# divisor.net
KiCad netlist of a schematic drawn in Altium Designer
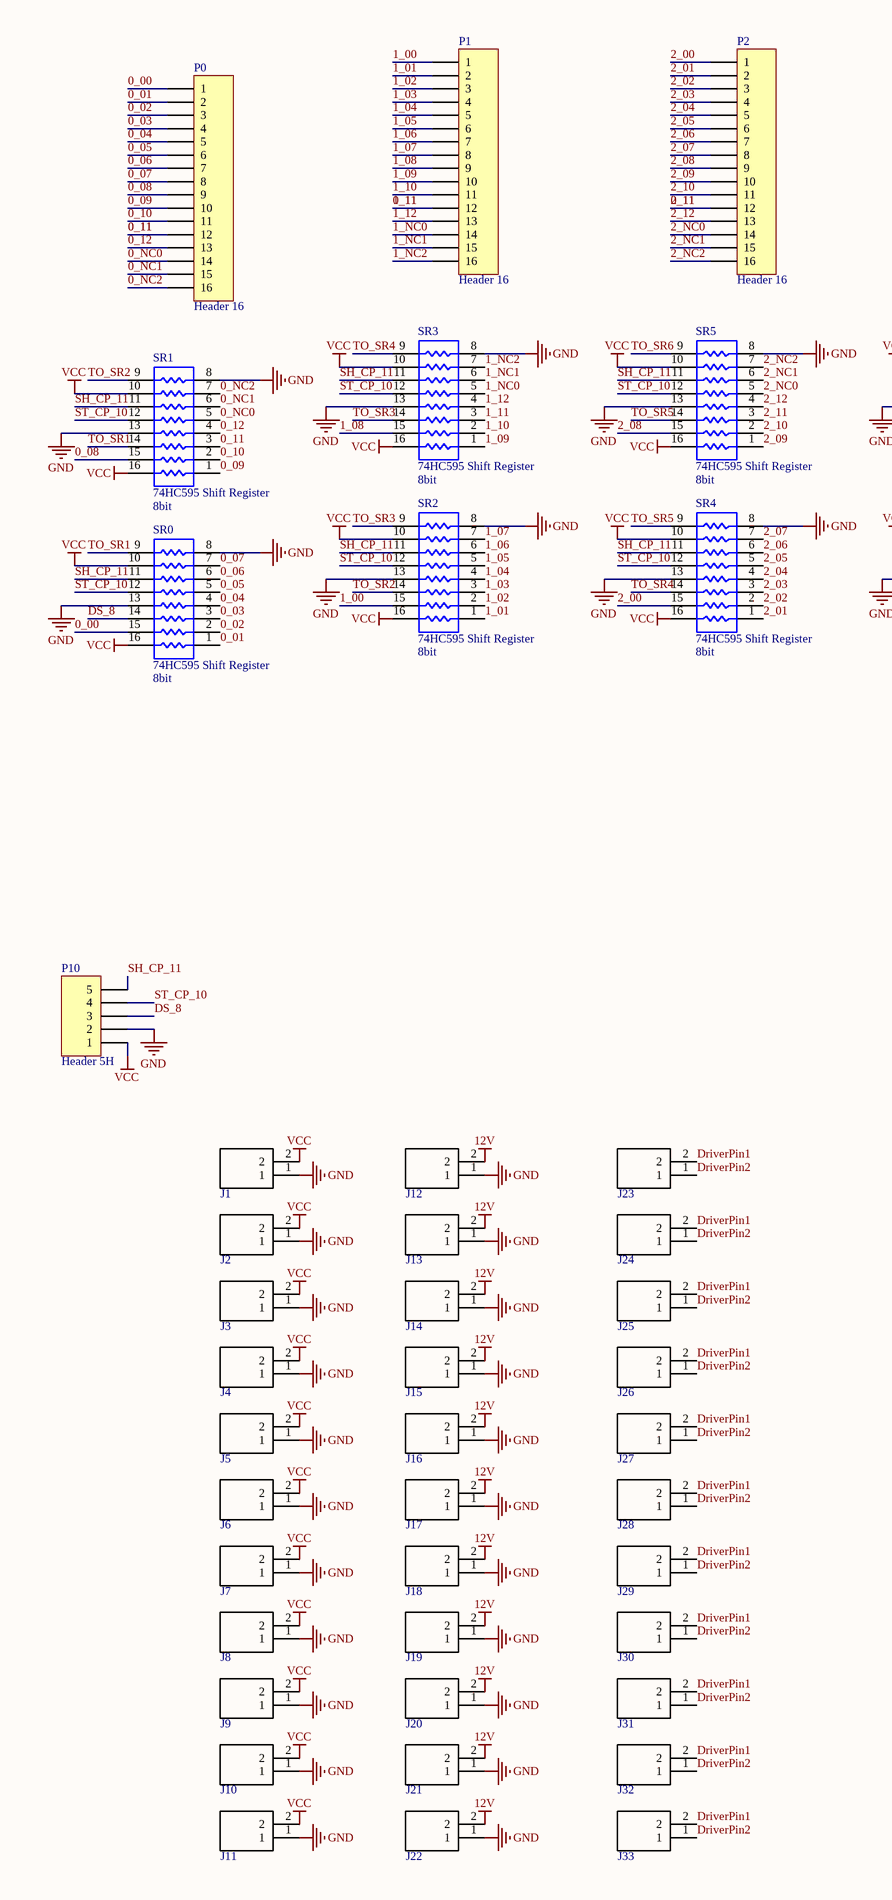
[diagram p0: divisor.SchDoc, left]
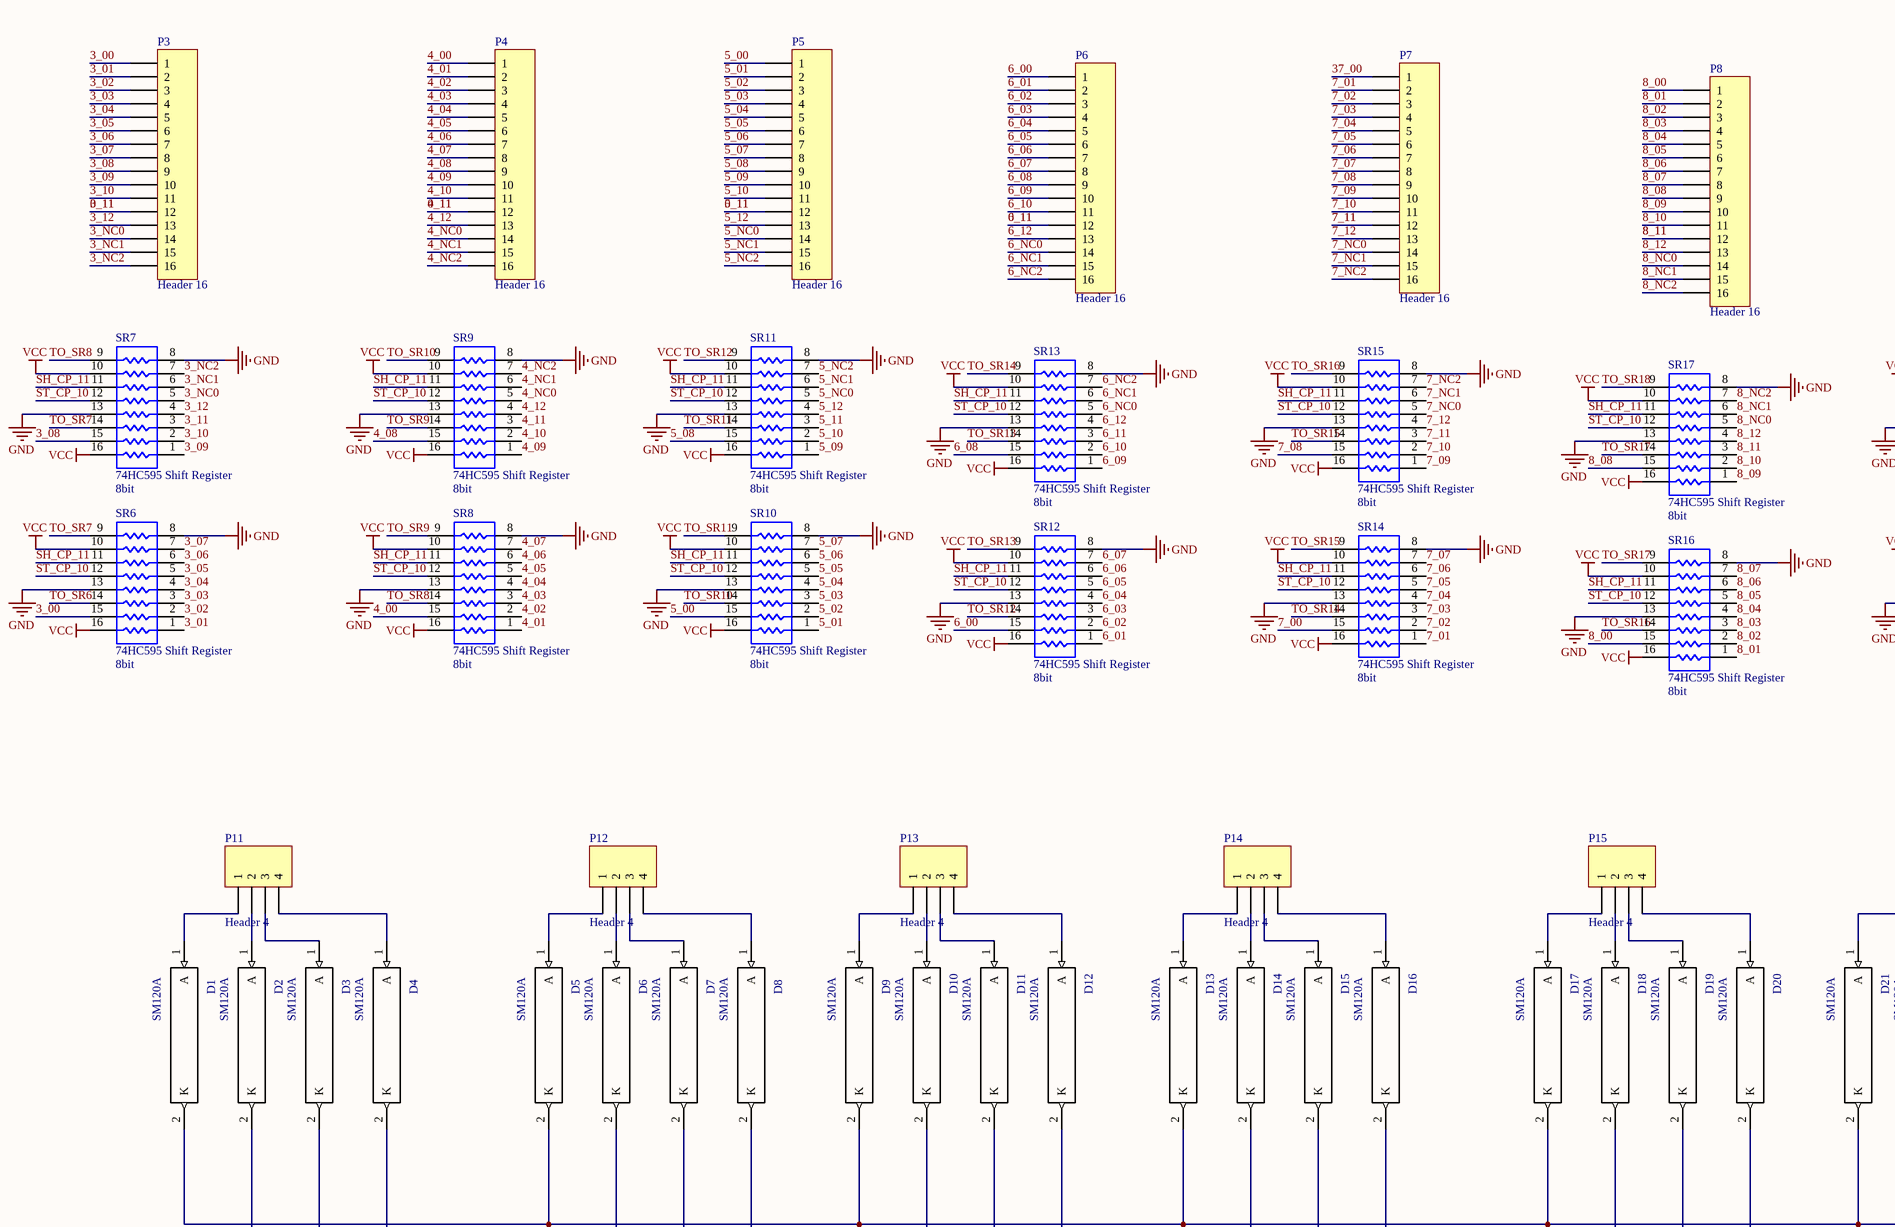
[diagram p1: divisor.SchDoc, middle]
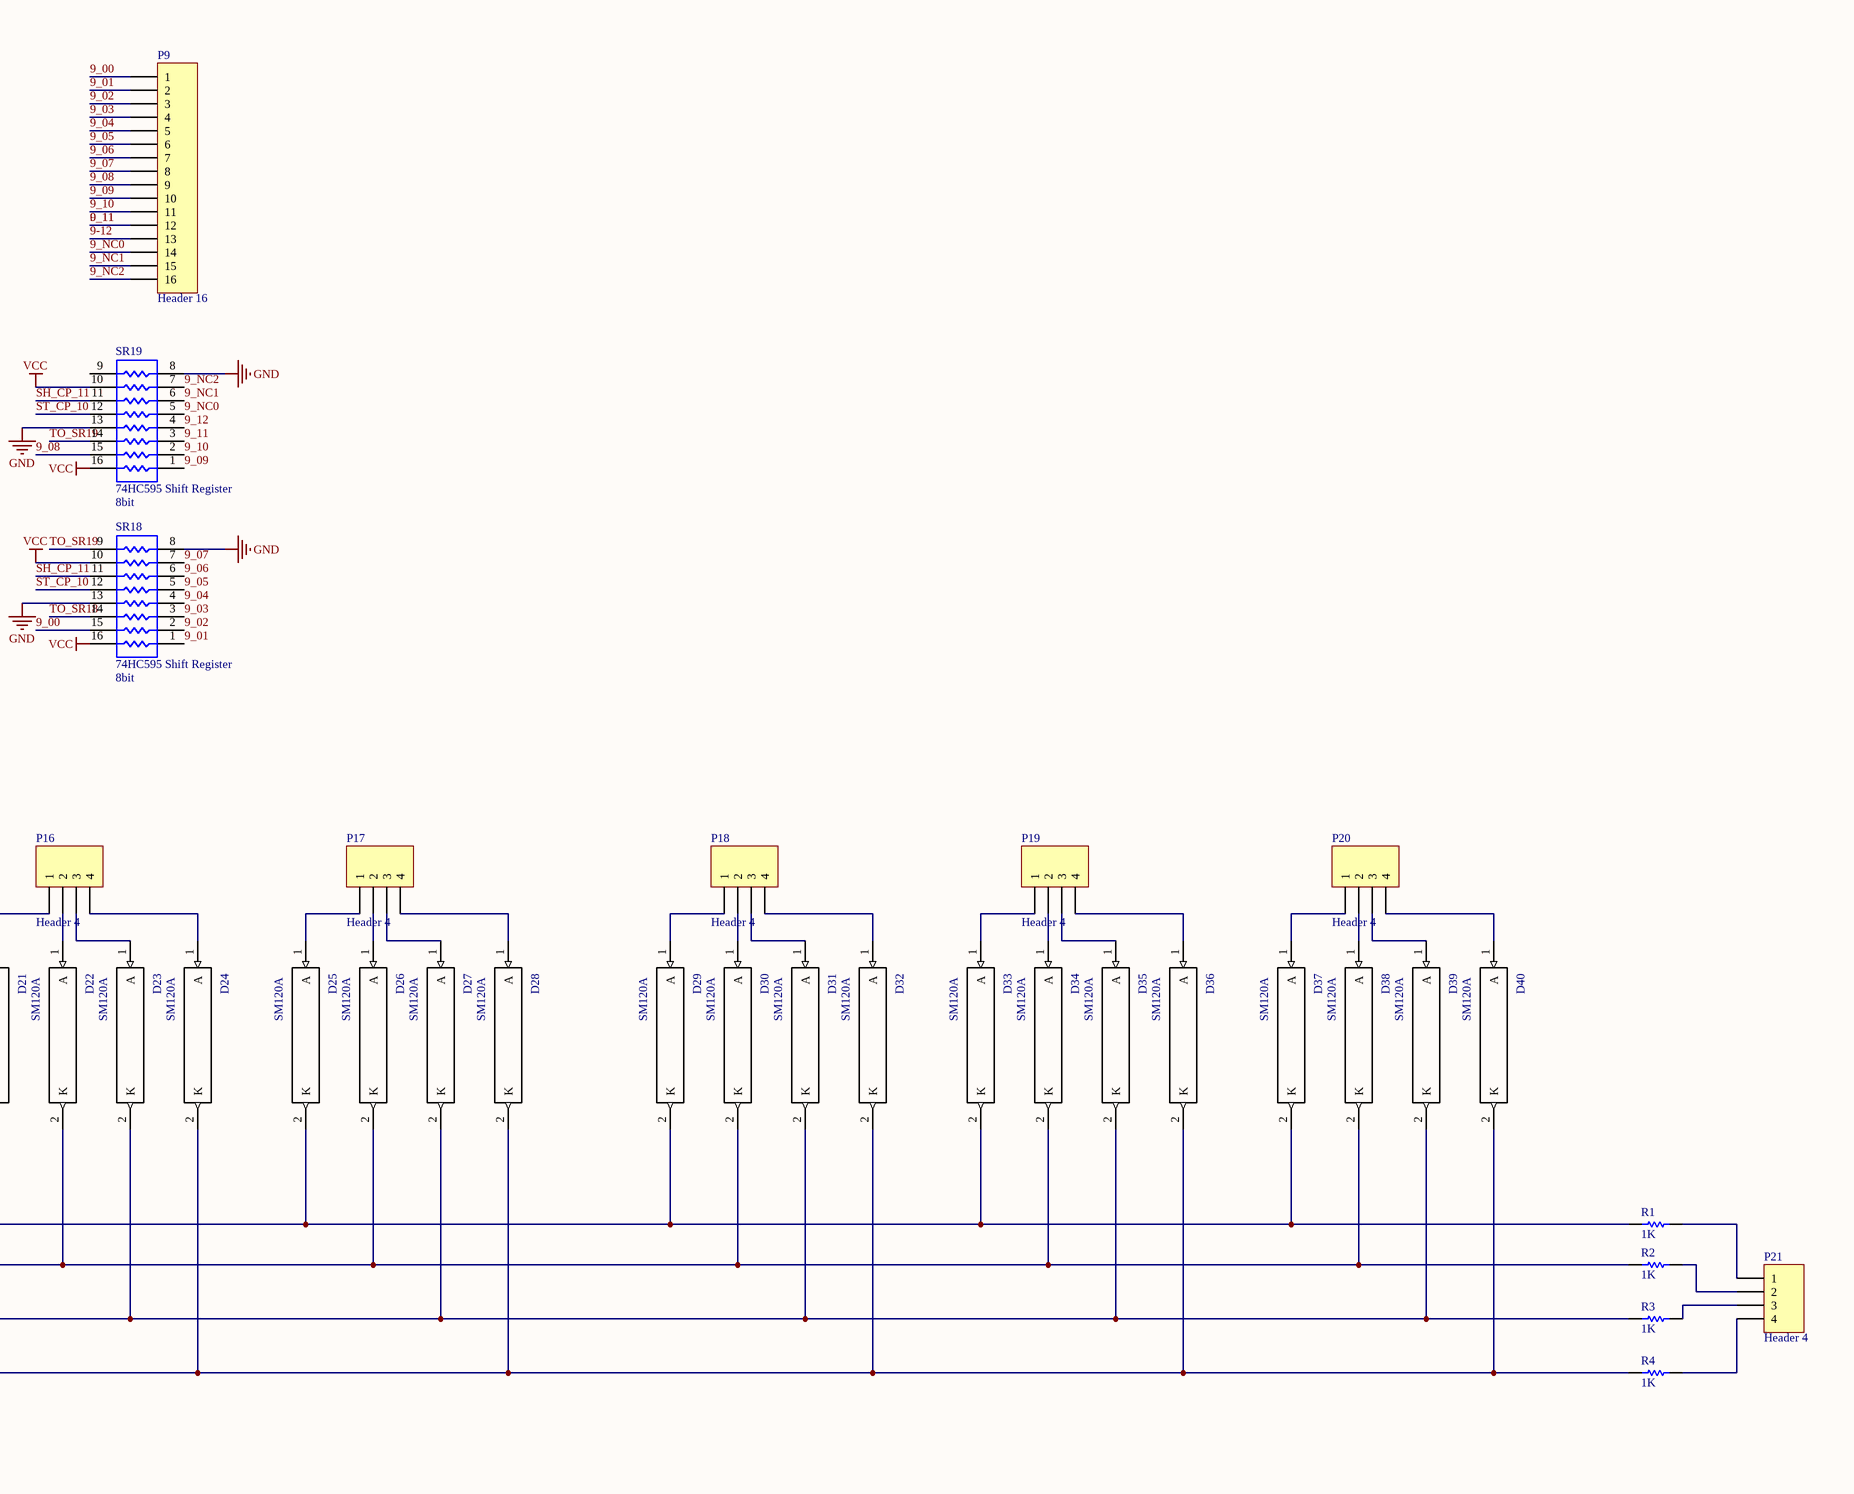
[diagram p2: divisor.SchDoc, right]

(export (version "E")
  (design (tool "Eeschema 10.0.6"))
  (components
    (comp (ref "D1")
      (value "SM120A")
      (footprint "*DIOM5227X270N_S1M(Primary)")
      (description "SCHOTTKY RECTIFIER 2A; Voltage Vrrm: 60V; Diode Case Style: DO-214AC; Case Style: DO-214AC")
      (fields (field (name "MF") "STMicroelectronics") (field (name "MP") "STPS2L60A"))
      (libsource (lib "STPS2L60A") (part "STPS2L60A"))
    )
    (comp (ref "D2")
      (value "SM120A")
      (footprint "*DIOM5227X270N_S1M(Primary)")
      (description "SCHOTTKY RECTIFIER 2A; Voltage Vrrm: 60V; Diode Case Style: DO-214AC; Case Style: DO-214AC")
      (fields (field (name "MF") "STMicroelectronics") (field (name "MP") "STPS2L60A"))
      (libsource (lib "STPS2L60A") (part "STPS2L60A"))
    )
    (comp (ref "D3")
      (value "SM120A")
      (footprint "*DIOM5227X270N_S1M(Primary)")
      (description "SCHOTTKY RECTIFIER 2A; Voltage Vrrm: 60V; Diode Case Style: DO-214AC; Case Style: DO-214AC")
      (fields (field (name "MF") "STMicroelectronics") (field (name "MP") "STPS2L60A"))
      (libsource (lib "STPS2L60A") (part "STPS2L60A"))
    )
    (comp (ref "D4")
      (value "SM120A")
      (footprint "*DIOM5227X270N_S1M(Primary)")
      (description "SCHOTTKY RECTIFIER 2A; Voltage Vrrm: 60V; Diode Case Style: DO-214AC; Case Style: DO-214AC")
      (fields (field (name "MF") "STMicroelectronics") (field (name "MP") "STPS2L60A"))
      (libsource (lib "STPS2L60A") (part "STPS2L60A"))
    )
    (comp (ref "D5")
      (value "SM120A")
      (footprint "*DIOM5227X270N_S1M(Primary)")
      (description "SCHOTTKY RECTIFIER 2A; Voltage Vrrm: 60V; Diode Case Style: DO-214AC; Case Style: DO-214AC")
      (fields (field (name "MF") "STMicroelectronics") (field (name "MP") "STPS2L60A"))
      (libsource (lib "STPS2L60A") (part "STPS2L60A"))
    )
    (comp (ref "D6")
      (value "SM120A")
      (footprint "*DIOM5227X270N_S1M(Primary)")
      (description "SCHOTTKY RECTIFIER 2A; Voltage Vrrm: 60V; Diode Case Style: DO-214AC; Case Style: DO-214AC")
      (fields (field (name "MF") "STMicroelectronics") (field (name "MP") "STPS2L60A"))
      (libsource (lib "STPS2L60A") (part "STPS2L60A"))
    )
    (comp (ref "D7")
      (value "SM120A")
      (footprint "*DIOM5227X270N_S1M(Primary)")
      (description "SCHOTTKY RECTIFIER 2A; Voltage Vrrm: 60V; Diode Case Style: DO-214AC; Case Style: DO-214AC")
      (fields (field (name "MF") "STMicroelectronics") (field (name "MP") "STPS2L60A"))
      (libsource (lib "STPS2L60A") (part "STPS2L60A"))
    )
    (comp (ref "D8")
      (value "SM120A")
      (footprint "*DIOM5227X270N_S1M(Primary)")
      (description "SCHOTTKY RECTIFIER 2A; Voltage Vrrm: 60V; Diode Case Style: DO-214AC; Case Style: DO-214AC")
      (fields (field (name "MF") "STMicroelectronics") (field (name "MP") "STPS2L60A"))
      (libsource (lib "STPS2L60A") (part "STPS2L60A"))
    )
    (comp (ref "D9")
      (value "SM120A")
      (footprint "*DIOM5227X270N_S1M(Primary)")
      (description "SCHOTTKY RECTIFIER 2A; Voltage Vrrm: 60V; Diode Case Style: DO-214AC; Case Style: DO-214AC")
      (fields (field (name "MF") "STMicroelectronics") (field (name "MP") "STPS2L60A"))
      (libsource (lib "STPS2L60A") (part "STPS2L60A"))
    )
    (comp (ref "D10")
      (value "SM120A")
      (footprint "*DIOM5227X270N_S1M(Primary)")
      (description "SCHOTTKY RECTIFIER 2A; Voltage Vrrm: 60V; Diode Case Style: DO-214AC; Case Style: DO-214AC")
      (fields (field (name "MF") "STMicroelectronics") (field (name "MP") "STPS2L60A"))
      (libsource (lib "STPS2L60A") (part "STPS2L60A"))
    )
    (comp (ref "D11")
      (value "SM120A")
      (footprint "*DIOM5227X270N_S1M(Primary)")
      (description "SCHOTTKY RECTIFIER 2A; Voltage Vrrm: 60V; Diode Case Style: DO-214AC; Case Style: DO-214AC")
      (fields (field (name "MF") "STMicroelectronics") (field (name "MP") "STPS2L60A"))
      (libsource (lib "STPS2L60A") (part "STPS2L60A"))
    )
    (comp (ref "D12")
      (value "SM120A")
      (footprint "*DIOM5227X270N_S1M(Primary)")
      (description "SCHOTTKY RECTIFIER 2A; Voltage Vrrm: 60V; Diode Case Style: DO-214AC; Case Style: DO-214AC")
      (fields (field (name "MF") "STMicroelectronics") (field (name "MP") "STPS2L60A"))
      (libsource (lib "STPS2L60A") (part "STPS2L60A"))
    )
    (comp (ref "D13")
      (value "SM120A")
      (footprint "*DIOM5227X270N_S1M(Primary)")
      (description "SCHOTTKY RECTIFIER 2A; Voltage Vrrm: 60V; Diode Case Style: DO-214AC; Case Style: DO-214AC")
      (fields (field (name "MF") "STMicroelectronics") (field (name "MP") "STPS2L60A"))
      (libsource (lib "STPS2L60A") (part "STPS2L60A"))
    )
    (comp (ref "D14")
      (value "SM120A")
      (footprint "*DIOM5227X270N_S1M(Primary)")
      (description "SCHOTTKY RECTIFIER 2A; Voltage Vrrm: 60V; Diode Case Style: DO-214AC; Case Style: DO-214AC")
      (fields (field (name "MF") "STMicroelectronics") (field (name "MP") "STPS2L60A"))
      (libsource (lib "STPS2L60A") (part "STPS2L60A"))
    )
    (comp (ref "D15")
      (value "SM120A")
      (footprint "*DIOM5227X270N_S1M(Primary)")
      (description "SCHOTTKY RECTIFIER 2A; Voltage Vrrm: 60V; Diode Case Style: DO-214AC; Case Style: DO-214AC")
      (fields (field (name "MF") "STMicroelectronics") (field (name "MP") "STPS2L60A"))
      (libsource (lib "STPS2L60A") (part "STPS2L60A"))
    )
    (comp (ref "D16")
      (value "SM120A")
      (footprint "*DIOM5227X270N_S1M(Primary)")
      (description "SCHOTTKY RECTIFIER 2A; Voltage Vrrm: 60V; Diode Case Style: DO-214AC; Case Style: DO-214AC")
      (fields (field (name "MF") "STMicroelectronics") (field (name "MP") "STPS2L60A"))
      (libsource (lib "STPS2L60A") (part "STPS2L60A"))
    )
    (comp (ref "D17")
      (value "SM120A")
      (footprint "*DIOM5227X270N_S1M(Primary)")
      (description "SCHOTTKY RECTIFIER 2A; Voltage Vrrm: 60V; Diode Case Style: DO-214AC; Case Style: DO-214AC")
      (fields (field (name "MF") "STMicroelectronics") (field (name "MP") "STPS2L60A"))
      (libsource (lib "STPS2L60A") (part "STPS2L60A"))
    )
    (comp (ref "D18")
      (value "SM120A")
      (footprint "*DIOM5227X270N_S1M(Primary)")
      (description "SCHOTTKY RECTIFIER 2A; Voltage Vrrm: 60V; Diode Case Style: DO-214AC; Case Style: DO-214AC")
      (fields (field (name "MF") "STMicroelectronics") (field (name "MP") "STPS2L60A"))
      (libsource (lib "STPS2L60A") (part "STPS2L60A"))
    )
    (comp (ref "D19")
      (value "SM120A")
      (footprint "*DIOM5227X270N_S1M(Primary)")
      (description "SCHOTTKY RECTIFIER 2A; Voltage Vrrm: 60V; Diode Case Style: DO-214AC; Case Style: DO-214AC")
      (fields (field (name "MF") "STMicroelectronics") (field (name "MP") "STPS2L60A"))
      (libsource (lib "STPS2L60A") (part "STPS2L60A"))
    )
    (comp (ref "D20")
      (value "SM120A")
      (footprint "*DIOM5227X270N_S1M(Primary)")
      (description "SCHOTTKY RECTIFIER 2A; Voltage Vrrm: 60V; Diode Case Style: DO-214AC; Case Style: DO-214AC")
      (fields (field (name "MF") "STMicroelectronics") (field (name "MP") "STPS2L60A"))
      (libsource (lib "STPS2L60A") (part "STPS2L60A"))
    )
    (comp (ref "D21")
      (value "SM120A")
      (footprint "*DIOM5227X270N_S1M(Primary)")
      (description "SCHOTTKY RECTIFIER 2A; Voltage Vrrm: 60V; Diode Case Style: DO-214AC; Case Style: DO-214AC")
      (fields (field (name "MF") "STMicroelectronics") (field (name "MP") "STPS2L60A"))
      (libsource (lib "STPS2L60A") (part "STPS2L60A"))
    )
    (comp (ref "D22")
      (value "SM120A")
      (footprint "*DIOM5227X270N_S1M(Primary)")
      (description "SCHOTTKY RECTIFIER 2A; Voltage Vrrm: 60V; Diode Case Style: DO-214AC; Case Style: DO-214AC")
      (fields (field (name "MF") "STMicroelectronics") (field (name "MP") "STPS2L60A"))
      (libsource (lib "STPS2L60A") (part "STPS2L60A"))
    )
    (comp (ref "D23")
      (value "SM120A")
      (footprint "*DIOM5227X270N_S1M(Primary)")
      (description "SCHOTTKY RECTIFIER 2A; Voltage Vrrm: 60V; Diode Case Style: DO-214AC; Case Style: DO-214AC")
      (fields (field (name "MF") "STMicroelectronics") (field (name "MP") "STPS2L60A"))
      (libsource (lib "STPS2L60A") (part "STPS2L60A"))
    )
    (comp (ref "D24")
      (value "SM120A")
      (footprint "*DIOM5227X270N_S1M(Primary)")
      (description "SCHOTTKY RECTIFIER 2A; Voltage Vrrm: 60V; Diode Case Style: DO-214AC; Case Style: DO-214AC")
      (fields (field (name "MF") "STMicroelectronics") (field (name "MP") "STPS2L60A"))
      (libsource (lib "STPS2L60A") (part "STPS2L60A"))
    )
    (comp (ref "D25")
      (value "SM120A")
      (footprint "*DIOM5227X270N_S1M(Primary)")
      (description "SCHOTTKY RECTIFIER 2A; Voltage Vrrm: 60V; Diode Case Style: DO-214AC; Case Style: DO-214AC")
      (fields (field (name "MF") "STMicroelectronics") (field (name "MP") "STPS2L60A"))
      (libsource (lib "STPS2L60A") (part "STPS2L60A"))
    )
    (comp (ref "D26")
      (value "SM120A")
      (footprint "*DIOM5227X270N_S1M(Primary)")
      (description "SCHOTTKY RECTIFIER 2A; Voltage Vrrm: 60V; Diode Case Style: DO-214AC; Case Style: DO-214AC")
      (fields (field (name "MF") "STMicroelectronics") (field (name "MP") "STPS2L60A"))
      (libsource (lib "STPS2L60A") (part "STPS2L60A"))
    )
    (comp (ref "D27")
      (value "SM120A")
      (footprint "*DIOM5227X270N_S1M(Primary)")
      (description "SCHOTTKY RECTIFIER 2A; Voltage Vrrm: 60V; Diode Case Style: DO-214AC; Case Style: DO-214AC")
      (fields (field (name "MF") "STMicroelectronics") (field (name "MP") "STPS2L60A"))
      (libsource (lib "STPS2L60A") (part "STPS2L60A"))
    )
    (comp (ref "D28")
      (value "SM120A")
      (footprint "*DIOM5227X270N_S1M(Primary)")
      (description "SCHOTTKY RECTIFIER 2A; Voltage Vrrm: 60V; Diode Case Style: DO-214AC; Case Style: DO-214AC")
      (fields (field (name "MF") "STMicroelectronics") (field (name "MP") "STPS2L60A"))
      (libsource (lib "STPS2L60A") (part "STPS2L60A"))
    )
    (comp (ref "D29")
      (value "SM120A")
      (footprint "*DIOM5227X270N_S1M(Primary)")
      (description "SCHOTTKY RECTIFIER 2A; Voltage Vrrm: 60V; Diode Case Style: DO-214AC; Case Style: DO-214AC")
      (fields (field (name "MF") "STMicroelectronics") (field (name "MP") "STPS2L60A"))
      (libsource (lib "STPS2L60A") (part "STPS2L60A"))
    )
    (comp (ref "D30")
      (value "SM120A")
      (footprint "*DIOM5227X270N_S1M(Primary)")
      (description "SCHOTTKY RECTIFIER 2A; Voltage Vrrm: 60V; Diode Case Style: DO-214AC; Case Style: DO-214AC")
      (fields (field (name "MF") "STMicroelectronics") (field (name "MP") "STPS2L60A"))
      (libsource (lib "STPS2L60A") (part "STPS2L60A"))
    )
    (comp (ref "D31")
      (value "SM120A")
      (footprint "*DIOM5227X270N_S1M(Primary)")
      (description "SCHOTTKY RECTIFIER 2A; Voltage Vrrm: 60V; Diode Case Style: DO-214AC; Case Style: DO-214AC")
      (fields (field (name "MF") "STMicroelectronics") (field (name "MP") "STPS2L60A"))
      (libsource (lib "STPS2L60A") (part "STPS2L60A"))
    )
    (comp (ref "D32")
      (value "SM120A")
      (footprint "*DIOM5227X270N_S1M(Primary)")
      (description "SCHOTTKY RECTIFIER 2A; Voltage Vrrm: 60V; Diode Case Style: DO-214AC; Case Style: DO-214AC")
      (fields (field (name "MF") "STMicroelectronics") (field (name "MP") "STPS2L60A"))
      (libsource (lib "STPS2L60A") (part "STPS2L60A"))
    )
    (comp (ref "D33")
      (value "SM120A")
      (footprint "*DIOM5227X270N_S1M(Primary)")
      (description "SCHOTTKY RECTIFIER 2A; Voltage Vrrm: 60V; Diode Case Style: DO-214AC; Case Style: DO-214AC")
      (fields (field (name "MF") "STMicroelectronics") (field (name "MP") "STPS2L60A"))
      (libsource (lib "STPS2L60A") (part "STPS2L60A"))
    )
    (comp (ref "D34")
      (value "SM120A")
      (footprint "*DIOM5227X270N_S1M(Primary)")
      (description "SCHOTTKY RECTIFIER 2A; Voltage Vrrm: 60V; Diode Case Style: DO-214AC; Case Style: DO-214AC")
      (fields (field (name "MF") "STMicroelectronics") (field (name "MP") "STPS2L60A"))
      (libsource (lib "STPS2L60A") (part "STPS2L60A"))
    )
    (comp (ref "D35")
      (value "SM120A")
      (footprint "*DIOM5227X270N_S1M(Primary)")
      (description "SCHOTTKY RECTIFIER 2A; Voltage Vrrm: 60V; Diode Case Style: DO-214AC; Case Style: DO-214AC")
      (fields (field (name "MF") "STMicroelectronics") (field (name "MP") "STPS2L60A"))
      (libsource (lib "STPS2L60A") (part "STPS2L60A"))
    )
    (comp (ref "D36")
      (value "SM120A")
      (footprint "*DIOM5227X270N_S1M(Primary)")
      (description "SCHOTTKY RECTIFIER 2A; Voltage Vrrm: 60V; Diode Case Style: DO-214AC; Case Style: DO-214AC")
      (fields (field (name "MF") "STMicroelectronics") (field (name "MP") "STPS2L60A"))
      (libsource (lib "STPS2L60A") (part "STPS2L60A"))
    )
    (comp (ref "D37")
      (value "SM120A")
      (footprint "*DIOM5227X270N_S1M(Primary)")
      (description "SCHOTTKY RECTIFIER 2A; Voltage Vrrm: 60V; Diode Case Style: DO-214AC; Case Style: DO-214AC")
      (fields (field (name "MF") "STMicroelectronics") (field (name "MP") "STPS2L60A"))
      (libsource (lib "STPS2L60A") (part "STPS2L60A"))
    )
    (comp (ref "D38")
      (value "SM120A")
      (footprint "*DIOM5227X270N_S1M(Primary)")
      (description "SCHOTTKY RECTIFIER 2A; Voltage Vrrm: 60V; Diode Case Style: DO-214AC; Case Style: DO-214AC")
      (fields (field (name "MF") "STMicroelectronics") (field (name "MP") "STPS2L60A"))
      (libsource (lib "STPS2L60A") (part "STPS2L60A"))
    )
    (comp (ref "D39")
      (value "SM120A")
      (footprint "*DIOM5227X270N_S1M(Primary)")
      (description "SCHOTTKY RECTIFIER 2A; Voltage Vrrm: 60V; Diode Case Style: DO-214AC; Case Style: DO-214AC")
      (fields (field (name "MF") "STMicroelectronics") (field (name "MP") "STPS2L60A"))
      (libsource (lib "STPS2L60A") (part "STPS2L60A"))
    )
    (comp (ref "D40")
      (value "SM120A")
      (footprint "*DIOM5227X270N_S1M(Primary)")
      (description "SCHOTTKY RECTIFIER 2A; Voltage Vrrm: 60V; Diode Case Style: DO-214AC; Case Style: DO-214AC")
      (fields (field (name "MF") "STMicroelectronics") (field (name "MP") "STPS2L60A"))
      (libsource (lib "STPS2L60A") (part "STPS2L60A"))
    )
    (comp (ref "J1")
      (value "6-1123723-2")
      (footprint "*TE_6-1123723-2")
      (description "3.96 EP HDR ASSY 2P_GREEN_")
      (fields (field (name "MF") "TE Connectivity"))
      (libsource (lib "6-1123723-2") (part "6-1123723-2"))
    )
    (comp (ref "J2")
      (value "6-1123723-2")
      (footprint "*TE_6-1123723-2")
      (description "3.96 EP HDR ASSY 2P_GREEN_")
      (fields (field (name "MF") "TE Connectivity"))
      (libsource (lib "6-1123723-2") (part "6-1123723-2"))
    )
    (comp (ref "J3")
      (value "6-1123723-2")
      (footprint "*TE_6-1123723-2")
      (description "3.96 EP HDR ASSY 2P_GREEN_")
      (fields (field (name "MF") "TE Connectivity"))
      (libsource (lib "6-1123723-2") (part "6-1123723-2"))
    )
    (comp (ref "J4")
      (value "6-1123723-2")
      (footprint "*TE_6-1123723-2")
      (description "3.96 EP HDR ASSY 2P_GREEN_")
      (fields (field (name "MF") "TE Connectivity"))
      (libsource (lib "6-1123723-2") (part "6-1123723-2"))
    )
    (comp (ref "J5")
      (value "6-1123723-2")
      (footprint "*TE_6-1123723-2")
      (description "3.96 EP HDR ASSY 2P_GREEN_")
      (fields (field (name "MF") "TE Connectivity"))
      (libsource (lib "6-1123723-2") (part "6-1123723-2"))
    )
    (comp (ref "J6")
      (value "6-1123723-2")
      (footprint "*TE_6-1123723-2")
      (description "3.96 EP HDR ASSY 2P_GREEN_")
      (fields (field (name "MF") "TE Connectivity"))
      (libsource (lib "6-1123723-2") (part "6-1123723-2"))
    )
    (comp (ref "J7")
      (value "6-1123723-2")
      (footprint "*TE_6-1123723-2")
      (description "3.96 EP HDR ASSY 2P_GREEN_")
      (fields (field (name "MF") "TE Connectivity"))
      (libsource (lib "6-1123723-2") (part "6-1123723-2"))
    )
    (comp (ref "J8")
      (value "6-1123723-2")
      (footprint "*TE_6-1123723-2")
      (description "3.96 EP HDR ASSY 2P_GREEN_")
      (fields (field (name "MF") "TE Connectivity"))
      (libsource (lib "6-1123723-2") (part "6-1123723-2"))
    )
    (comp (ref "J9")
      (value "6-1123723-2")
      (footprint "*TE_6-1123723-2")
      (description "3.96 EP HDR ASSY 2P_GREEN_")
      (fields (field (name "MF") "TE Connectivity"))
      (libsource (lib "6-1123723-2") (part "6-1123723-2"))
    )
    (comp (ref "J10")
      (value "6-1123723-2")
      (footprint "*TE_6-1123723-2")
      (description "3.96 EP HDR ASSY 2P_GREEN_")
      (fields (field (name "MF") "TE Connectivity"))
      (libsource (lib "6-1123723-2") (part "6-1123723-2"))
    )
    (comp (ref "J11")
      (value "6-1123723-2")
      (footprint "*TE_6-1123723-2")
      (description "3.96 EP HDR ASSY 2P_GREEN_")
      (fields (field (name "MF") "TE Connectivity"))
      (libsource (lib "6-1123723-2") (part "6-1123723-2"))
    )
    (comp (ref "J12")
      (value "6-1123723-2")
      (footprint "*TE_6-1123723-2")
      (description "3.96 EP HDR ASSY 2P_GREEN_")
      (fields (field (name "MF") "TE Connectivity"))
      (libsource (lib "6-1123723-2") (part "6-1123723-2"))
    )
    (comp (ref "J13")
      (value "6-1123723-2")
      (footprint "*TE_6-1123723-2")
      (description "3.96 EP HDR ASSY 2P_GREEN_")
      (fields (field (name "MF") "TE Connectivity"))
      (libsource (lib "6-1123723-2") (part "6-1123723-2"))
    )
    (comp (ref "J14")
      (value "6-1123723-2")
      (footprint "*TE_6-1123723-2")
      (description "3.96 EP HDR ASSY 2P_GREEN_")
      (fields (field (name "MF") "TE Connectivity"))
      (libsource (lib "6-1123723-2") (part "6-1123723-2"))
    )
    (comp (ref "J15")
      (value "6-1123723-2")
      (footprint "*TE_6-1123723-2")
      (description "3.96 EP HDR ASSY 2P_GREEN_")
      (fields (field (name "MF") "TE Connectivity"))
      (libsource (lib "6-1123723-2") (part "6-1123723-2"))
    )
    (comp (ref "J16")
      (value "6-1123723-2")
      (footprint "*TE_6-1123723-2")
      (description "3.96 EP HDR ASSY 2P_GREEN_")
      (fields (field (name "MF") "TE Connectivity"))
      (libsource (lib "6-1123723-2") (part "6-1123723-2"))
    )
    (comp (ref "J17")
      (value "6-1123723-2")
      (footprint "*TE_6-1123723-2")
      (description "3.96 EP HDR ASSY 2P_GREEN_")
      (fields (field (name "MF") "TE Connectivity"))
      (libsource (lib "6-1123723-2") (part "6-1123723-2"))
    )
    (comp (ref "J18")
      (value "6-1123723-2")
      (footprint "*TE_6-1123723-2")
      (description "3.96 EP HDR ASSY 2P_GREEN_")
      (fields (field (name "MF") "TE Connectivity"))
      (libsource (lib "6-1123723-2") (part "6-1123723-2"))
    )
    (comp (ref "J19")
      (value "6-1123723-2")
      (footprint "*TE_6-1123723-2")
      (description "3.96 EP HDR ASSY 2P_GREEN_")
      (fields (field (name "MF") "TE Connectivity"))
      (libsource (lib "6-1123723-2") (part "6-1123723-2"))
    )
    (comp (ref "J20")
      (value "6-1123723-2")
      (footprint "*TE_6-1123723-2")
      (description "3.96 EP HDR ASSY 2P_GREEN_")
      (fields (field (name "MF") "TE Connectivity"))
      (libsource (lib "6-1123723-2") (part "6-1123723-2"))
    )
    (comp (ref "J21")
      (value "6-1123723-2")
      (footprint "*TE_6-1123723-2")
      (description "3.96 EP HDR ASSY 2P_GREEN_")
      (fields (field (name "MF") "TE Connectivity"))
      (libsource (lib "6-1123723-2") (part "6-1123723-2"))
    )
    (comp (ref "J22")
      (value "6-1123723-2")
      (footprint "*TE_6-1123723-2")
      (description "3.96 EP HDR ASSY 2P_GREEN_")
      (fields (field (name "MF") "TE Connectivity"))
      (libsource (lib "6-1123723-2") (part "6-1123723-2"))
    )
    (comp (ref "J23")
      (value "6-1123723-2")
      (footprint "*TE_6-1123723-2")
      (description "3.96 EP HDR ASSY 2P_GREEN_")
      (fields (field (name "MF") "TE Connectivity"))
      (libsource (lib "6-1123723-2") (part "6-1123723-2"))
    )
    (comp (ref "J24")
      (value "6-1123723-2")
      (footprint "*TE_6-1123723-2")
      (description "3.96 EP HDR ASSY 2P_GREEN_")
      (fields (field (name "MF") "TE Connectivity"))
      (libsource (lib "6-1123723-2") (part "6-1123723-2"))
    )
    (comp (ref "J25")
      (value "6-1123723-2")
      (footprint "*TE_6-1123723-2")
      (description "3.96 EP HDR ASSY 2P_GREEN_")
      (fields (field (name "MF") "TE Connectivity"))
      (libsource (lib "6-1123723-2") (part "6-1123723-2"))
    )
    (comp (ref "J26")
      (value "6-1123723-2")
      (footprint "*TE_6-1123723-2")
      (description "3.96 EP HDR ASSY 2P_GREEN_")
      (fields (field (name "MF") "TE Connectivity"))
      (libsource (lib "6-1123723-2") (part "6-1123723-2"))
    )
    (comp (ref "J27")
      (value "6-1123723-2")
      (footprint "*TE_6-1123723-2")
      (description "3.96 EP HDR ASSY 2P_GREEN_")
      (fields (field (name "MF") "TE Connectivity"))
      (libsource (lib "6-1123723-2") (part "6-1123723-2"))
    )
    (comp (ref "J28")
      (value "6-1123723-2")
      (footprint "*TE_6-1123723-2")
      (description "3.96 EP HDR ASSY 2P_GREEN_")
      (fields (field (name "MF") "TE Connectivity"))
      (libsource (lib "6-1123723-2") (part "6-1123723-2"))
    )
    (comp (ref "J29")
      (value "6-1123723-2")
      (footprint "*TE_6-1123723-2")
      (description "3.96 EP HDR ASSY 2P_GREEN_")
      (fields (field (name "MF") "TE Connectivity"))
      (libsource (lib "6-1123723-2") (part "6-1123723-2"))
    )
    (comp (ref "J30")
      (value "6-1123723-2")
      (footprint "*TE_6-1123723-2")
      (description "3.96 EP HDR ASSY 2P_GREEN_")
      (fields (field (name "MF") "TE Connectivity"))
      (libsource (lib "6-1123723-2") (part "6-1123723-2"))
    )
    (comp (ref "J31")
      (value "6-1123723-2")
      (footprint "*TE_6-1123723-2")
      (description "3.96 EP HDR ASSY 2P_GREEN_")
      (fields (field (name "MF") "TE Connectivity"))
      (libsource (lib "6-1123723-2") (part "6-1123723-2"))
    )
    (comp (ref "J32")
      (value "6-1123723-2")
      (footprint "*TE_6-1123723-2")
      (description "3.96 EP HDR ASSY 2P_GREEN_")
      (fields (field (name "MF") "TE Connectivity"))
      (libsource (lib "6-1123723-2") (part "6-1123723-2"))
    )
    (comp (ref "J33")
      (value "6-1123723-2")
      (footprint "*TE_6-1123723-2")
      (description "3.96 EP HDR ASSY 2P_GREEN_")
      (fields (field (name "MF") "TE Connectivity"))
      (libsource (lib "6-1123723-2") (part "6-1123723-2"))
    )
    (comp (ref "P0")
      (value "Header 16")
      (footprint "HDR1X16")
      (description "Header, 16-Pin")
      (fields (field (name "PUBLISHER") "Altium Limited"))
      (libsource (lib "Miscellaneous Connectors") (part "Header 16"))
    )
    (comp (ref "P1")
      (value "Header 16")
      (footprint "HDR1X16")
      (description "Header, 16-Pin")
      (fields (field (name "PUBLISHER") "Altium Limited"))
      (libsource (lib "Miscellaneous Connectors") (part "Header 16"))
    )
    (comp (ref "P2")
      (value "Header 16")
      (footprint "HDR1X16")
      (description "Header, 16-Pin")
      (fields (field (name "PUBLISHER") "Altium Limited"))
      (libsource (lib "Miscellaneous Connectors") (part "Header 16"))
    )
    (comp (ref "P3")
      (value "Header 16")
      (footprint "HDR1X16")
      (description "Header, 16-Pin")
      (fields (field (name "PUBLISHER") "Altium Limited"))
      (libsource (lib "Miscellaneous Connectors") (part "Header 16"))
    )
    (comp (ref "P4")
      (value "Header 16")
      (footprint "HDR1X16")
      (description "Header, 16-Pin")
      (fields (field (name "PUBLISHER") "Altium Limited"))
      (libsource (lib "Miscellaneous Connectors") (part "Header 16"))
    )
    (comp (ref "P5")
      (value "Header 16")
      (footprint "HDR1X16")
      (description "Header, 16-Pin")
      (fields (field (name "PUBLISHER") "Altium Limited"))
      (libsource (lib "Miscellaneous Connectors") (part "Header 16"))
    )
    (comp (ref "P6")
      (value "Header 16")
      (footprint "HDR1X16")
      (description "Header, 16-Pin")
      (fields (field (name "PUBLISHER") "Altium Limited"))
      (libsource (lib "Miscellaneous Connectors") (part "Header 16"))
    )
    (comp (ref "P7")
      (value "Header 16")
      (footprint "HDR1X16")
      (description "Header, 16-Pin")
      (fields (field (name "PUBLISHER") "Altium Limited"))
      (libsource (lib "Miscellaneous Connectors") (part "Header 16"))
    )
    (comp (ref "P8")
      (value "Header 16")
      (footprint "HDR1X16")
      (description "Header, 16-Pin")
      (fields (field (name "PUBLISHER") "Altium Limited"))
      (libsource (lib "Miscellaneous Connectors") (part "Header 16"))
    )
    (comp (ref "P9")
      (value "Header 16")
      (footprint "HDR1X16")
      (description "Header, 16-Pin")
      (fields (field (name "PUBLISHER") "Altium Limited"))
      (libsource (lib "Miscellaneous Connectors") (part "Header 16"))
    )
    (comp (ref "P10")
      (value "Header 5H")
      (footprint "hdr1x5")
      (description "Header, 5-Pin, Right Angle")
      (fields (field (name "PUBLISHER") "Altium Limited"))
      (libsource (lib "Miscellaneous Connectors") (part "Header 5H"))
    )
    (comp (ref "P11")
      (value "Header 4")
      (footprint "HDR1X4")
      (description "Header, 4-Pin")
      (fields (field (name "PUBLISHER") "Altium Limited"))
      (libsource (lib "Miscellaneous Connectors") (part "Header 4"))
    )
    (comp (ref "P12")
      (value "Header 4")
      (footprint "HDR1X4")
      (description "Header, 4-Pin")
      (fields (field (name "PUBLISHER") "Altium Limited"))
      (libsource (lib "Miscellaneous Connectors") (part "Header 4"))
    )
    (comp (ref "P13")
      (value "Header 4")
      (footprint "HDR1X4")
      (description "Header, 4-Pin")
      (fields (field (name "PUBLISHER") "Altium Limited"))
      (libsource (lib "Miscellaneous Connectors") (part "Header 4"))
    )
    (comp (ref "P14")
      (value "Header 4")
      (footprint "HDR1X4")
      (description "Header, 4-Pin")
      (fields (field (name "PUBLISHER") "Altium Limited"))
      (libsource (lib "Miscellaneous Connectors") (part "Header 4"))
    )
    (comp (ref "P15")
      (value "Header 4")
      (footprint "HDR1X4")
      (description "Header, 4-Pin")
      (fields (field (name "PUBLISHER") "Altium Limited"))
      (libsource (lib "Miscellaneous Connectors") (part "Header 4"))
    )
    (comp (ref "P16")
      (value "Header 4")
      (footprint "HDR1X4")
      (description "Header, 4-Pin")
      (fields (field (name "PUBLISHER") "Altium Limited"))
      (libsource (lib "Miscellaneous Connectors") (part "Header 4"))
    )
    (comp (ref "P17")
      (value "Header 4")
      (footprint "HDR1X4")
      (description "Header, 4-Pin")
      (fields (field (name "PUBLISHER") "Altium Limited"))
      (libsource (lib "Miscellaneous Connectors") (part "Header 4"))
    )
    (comp (ref "P18")
      (value "Header 4")
      (footprint "HDR1X4")
      (description "Header, 4-Pin")
      (fields (field (name "PUBLISHER") "Altium Limited"))
      (libsource (lib "Miscellaneous Connectors") (part "Header 4"))
    )
    (comp (ref "P19")
      (value "Header 4")
      (footprint "HDR1X4")
      (description "Header, 4-Pin")
      (fields (field (name "PUBLISHER") "Altium Limited"))
      (libsource (lib "Miscellaneous Connectors") (part "Header 4"))
    )
    (comp (ref "P20")
      (value "Header 4")
      (footprint "HDR1X4")
      (description "Header, 4-Pin")
      (fields (field (name "PUBLISHER") "Altium Limited"))
      (libsource (lib "Miscellaneous Connectors") (part "Header 4"))
    )
    (comp (ref "P21")
      (value "Header 4")
      (footprint "HDR1X4")
      (description "Header, 4-Pin")
      (fields (field (name "PUBLISHER") "Altium Limited"))
      (libsource (lib "") (part "Header 4_1"))
    )
    (comp (ref "R1")
      (value "1K")
      (footprint "6-0805_L")
      (description "Resistor")
      (fields (field (name "Comment") "Res1") (field (name "PUBLISHER") "Altium Limited"))
      (libsource (lib "Miscellaneous Devices") (part "Res1"))
    )
    (comp (ref "R2")
      (value "1K")
      (footprint "6-0805_L")
      (description "Resistor")
      (fields (field (name "Comment") "Res1") (field (name "PUBLISHER") "Altium Limited"))
      (libsource (lib "Miscellaneous Devices") (part "Res1"))
    )
    (comp (ref "R3")
      (value "1K")
      (footprint "6-0805_L")
      (description "Resistor")
      (fields (field (name "Comment") "Res1") (field (name "PUBLISHER") "Altium Limited"))
      (libsource (lib "Miscellaneous Devices") (part "Res1"))
    )
    (comp (ref "R4")
      (value "1K")
      (footprint "6-0805_L")
      (description "Resistor")
      (fields (field (name "Comment") "Res1") (field (name "PUBLISHER") "Altium Limited"))
      (libsource (lib "Miscellaneous Devices") (part "Res1"))
    )
    (comp (ref "SR0")
      (value "74HC595 Shift Register")
      (footprint "SO-16_L")
      (description "Isolated Resistor Network")
      (fields (field (name "ALTIUM_VALUE") "8bit") (field (name "PUBLISHER") "Altium Limited"))
      (libsource (lib "Miscellaneous Devices") (part "Res Pack3"))
    )
    (comp (ref "SR1")
      (value "74HC595 Shift Register")
      (footprint "SO-16_L")
      (description "Isolated Resistor Network")
      (fields (field (name "ALTIUM_VALUE") "8bit") (field (name "PUBLISHER") "Altium Limited"))
      (libsource (lib "Miscellaneous Devices") (part "Res Pack3"))
    )
    (comp (ref "SR2")
      (value "74HC595 Shift Register")
      (footprint "SO-16_L")
      (description "Isolated Resistor Network")
      (fields (field (name "ALTIUM_VALUE") "8bit") (field (name "PUBLISHER") "Altium Limited"))
      (libsource (lib "Miscellaneous Devices") (part "Res Pack3"))
    )
    (comp (ref "SR3")
      (value "74HC595 Shift Register")
      (footprint "SO-16_L")
      (description "Isolated Resistor Network")
      (fields (field (name "ALTIUM_VALUE") "8bit") (field (name "PUBLISHER") "Altium Limited"))
      (libsource (lib "Miscellaneous Devices") (part "Res Pack3"))
    )
    (comp (ref "SR4")
      (value "74HC595 Shift Register")
      (footprint "SO-16_L")
      (description "Isolated Resistor Network")
      (fields (field (name "ALTIUM_VALUE") "8bit") (field (name "PUBLISHER") "Altium Limited"))
      (libsource (lib "Miscellaneous Devices") (part "Res Pack3"))
    )
    (comp (ref "SR5")
      (value "74HC595 Shift Register")
      (footprint "SO-16_L")
      (description "Isolated Resistor Network")
      (fields (field (name "ALTIUM_VALUE") "8bit") (field (name "PUBLISHER") "Altium Limited"))
      (libsource (lib "Miscellaneous Devices") (part "Res Pack3"))
    )
    (comp (ref "SR6")
      (value "74HC595 Shift Register")
      (footprint "SO-16_L")
      (description "Isolated Resistor Network")
      (fields (field (name "ALTIUM_VALUE") "8bit") (field (name "PUBLISHER") "Altium Limited"))
      (libsource (lib "Miscellaneous Devices") (part "Res Pack3"))
    )
    (comp (ref "SR7")
      (value "74HC595 Shift Register")
      (footprint "SO-16_L")
      (description "Isolated Resistor Network")
      (fields (field (name "ALTIUM_VALUE") "8bit") (field (name "PUBLISHER") "Altium Limited"))
      (libsource (lib "Miscellaneous Devices") (part "Res Pack3"))
    )
    (comp (ref "SR8")
      (value "74HC595 Shift Register")
      (footprint "SO-16_L")
      (description "Isolated Resistor Network")
      (fields (field (name "ALTIUM_VALUE") "8bit") (field (name "PUBLISHER") "Altium Limited"))
      (libsource (lib "Miscellaneous Devices") (part "Res Pack3"))
    )
    (comp (ref "SR9")
      (value "74HC595 Shift Register")
      (footprint "SO-16_L")
      (description "Isolated Resistor Network")
      (fields (field (name "ALTIUM_VALUE") "8bit") (field (name "PUBLISHER") "Altium Limited"))
      (libsource (lib "Miscellaneous Devices") (part "Res Pack3"))
    )
    (comp (ref "SR10")
      (value "74HC595 Shift Register")
      (footprint "SO-16_L")
      (description "Isolated Resistor Network")
      (fields (field (name "ALTIUM_VALUE") "8bit") (field (name "PUBLISHER") "Altium Limited"))
      (libsource (lib "Miscellaneous Devices") (part "Res Pack3"))
    )
    (comp (ref "SR11")
      (value "74HC595 Shift Register")
      (footprint "SO-16_L")
      (description "Isolated Resistor Network")
      (fields (field (name "ALTIUM_VALUE") "8bit") (field (name "PUBLISHER") "Altium Limited"))
      (libsource (lib "Miscellaneous Devices") (part "Res Pack3"))
    )
    (comp (ref "SR12")
      (value "74HC595 Shift Register")
      (footprint "SO-16_L")
      (description "Isolated Resistor Network")
      (fields (field (name "ALTIUM_VALUE") "8bit") (field (name "PUBLISHER") "Altium Limited"))
      (libsource (lib "Miscellaneous Devices") (part "Res Pack3"))
    )
    (comp (ref "SR13")
      (value "74HC595 Shift Register")
      (footprint "SO-16_L")
      (description "Isolated Resistor Network")
      (fields (field (name "ALTIUM_VALUE") "8bit") (field (name "PUBLISHER") "Altium Limited"))
      (libsource (lib "Miscellaneous Devices") (part "Res Pack3"))
    )
    (comp (ref "SR14")
      (value "74HC595 Shift Register")
      (footprint "SO-16_L")
      (description "Isolated Resistor Network")
      (fields (field (name "ALTIUM_VALUE") "8bit") (field (name "PUBLISHER") "Altium Limited"))
      (libsource (lib "Miscellaneous Devices") (part "Res Pack3"))
    )
    (comp (ref "SR15")
      (value "74HC595 Shift Register")
      (footprint "SO-16_L")
      (description "Isolated Resistor Network")
      (fields (field (name "ALTIUM_VALUE") "8bit") (field (name "PUBLISHER") "Altium Limited"))
      (libsource (lib "Miscellaneous Devices") (part "Res Pack3"))
    )
    (comp (ref "SR16")
      (value "74HC595 Shift Register")
      (footprint "SO-16_L")
      (description "Isolated Resistor Network")
      (fields (field (name "ALTIUM_VALUE") "8bit") (field (name "PUBLISHER") "Altium Limited"))
      (libsource (lib "Miscellaneous Devices") (part "Res Pack3"))
    )
    (comp (ref "SR17")
      (value "74HC595 Shift Register")
      (footprint "SO-16_L")
      (description "Isolated Resistor Network")
      (fields (field (name "ALTIUM_VALUE") "8bit") (field (name "PUBLISHER") "Altium Limited"))
      (libsource (lib "Miscellaneous Devices") (part "Res Pack3"))
    )
    (comp (ref "SR18")
      (value "74HC595 Shift Register")
      (footprint "SO-16_L")
      (description "Isolated Resistor Network")
      (fields (field (name "ALTIUM_VALUE") "8bit") (field (name "PUBLISHER") "Altium Limited"))
      (libsource (lib "Miscellaneous Devices") (part "Res Pack3"))
    )
    (comp (ref "SR19")
      (value "74HC595 Shift Register")
      (footprint "SO-16_L")
      (description "Isolated Resistor Network")
      (fields (field (name "ALTIUM_VALUE") "8bit") (field (name "PUBLISHER") "Altium Limited"))
      (libsource (lib "Miscellaneous Devices") (part "Res Pack3"))
    )
  )
  (nets
    (net (code "1") (name "/0_00") (class "Default")
      (node (ref "P0") (pin "1") (pinfunction "1_1") (pintype "passive"))
      (node (ref "SR0") (pin "15") (pinfunction "15_15") (pintype "passive"))
    )
    (net (code "2") (name "/0_01") (class "Default")
      (node (ref "P0") (pin "2") (pinfunction "2_2") (pintype "passive"))
      (node (ref "SR0") (pin "1") (pinfunction "1_1") (pintype "passive"))
    )
    (net (code "3") (name "/0_02") (class "Default")
      (node (ref "P0") (pin "3") (pinfunction "3_3") (pintype "passive"))
      (node (ref "SR0") (pin "2") (pinfunction "2_2") (pintype "passive"))
    )
    (net (code "4") (name "/0_03") (class "Default")
      (node (ref "P0") (pin "4") (pinfunction "4_4") (pintype "passive"))
      (node (ref "SR0") (pin "3") (pinfunction "3_3") (pintype "passive"))
    )
    (net (code "5") (name "/0_04") (class "Default")
      (node (ref "P0") (pin "5") (pinfunction "5_5") (pintype "passive"))
      (node (ref "SR0") (pin "4") (pinfunction "4_4") (pintype "passive"))
    )
    (net (code "6") (name "/0_05") (class "Default")
      (node (ref "P0") (pin "6") (pinfunction "6_6") (pintype "passive"))
      (node (ref "SR0") (pin "5") (pinfunction "5_5") (pintype "passive"))
    )
    (net (code "7") (name "/0_06") (class "Default")
      (node (ref "P0") (pin "7") (pinfunction "7_7") (pintype "passive"))
      (node (ref "SR0") (pin "6") (pinfunction "6_6") (pintype "passive"))
    )
    (net (code "8") (name "/0_07") (class "Default")
      (node (ref "P0") (pin "8") (pinfunction "8_8") (pintype "passive"))
      (node (ref "SR0") (pin "7") (pinfunction "7_7") (pintype "passive"))
    )
    (net (code "9") (name "/0_08") (class "Default")
      (node (ref "P0") (pin "9") (pinfunction "9_9") (pintype "passive"))
      (node (ref "SR1") (pin "15") (pinfunction "15_15") (pintype "passive"))
    )
    (net (code "10") (name "/0_09") (class "Default")
      (node (ref "P0") (pin "10") (pinfunction "10_10") (pintype "passive"))
      (node (ref "SR1") (pin "1") (pinfunction "1_1") (pintype "passive"))
    )
    (net (code "11") (name "/0_10") (class "Default")
      (node (ref "P0") (pin "11") (pinfunction "11_11") (pintype "passive"))
      (node (ref "SR1") (pin "2") (pinfunction "2_2") (pintype "passive"))
    )
    (net (code "12") (name "/0_11") (class "Default")
      (node (ref "P0") (pin "12") (pinfunction "12_12") (pintype "passive"))
      (node (ref "P1") (pin "12") (pinfunction "12_12") (pintype "passive"))
      (node (ref "P2") (pin "12") (pinfunction "12_12") (pintype "passive"))
      (node (ref "P3") (pin "12") (pinfunction "12_12") (pintype "passive"))
      (node (ref "P4") (pin "12") (pinfunction "12_12") (pintype "passive"))
      (node (ref "P5") (pin "12") (pinfunction "12_12") (pintype "passive"))
      (node (ref "P6") (pin "12") (pinfunction "12_12") (pintype "passive"))
      (node (ref "P9") (pin "12") (pinfunction "12_12") (pintype "passive"))
      (node (ref "SR1") (pin "3") (pinfunction "3_3") (pintype "passive"))
      (node (ref "SR11") (pin "3") (pinfunction "3_3") (pintype "passive"))
      (node (ref "SR13") (pin "3") (pinfunction "3_3") (pintype "passive"))
      (node (ref "SR19") (pin "3") (pinfunction "3_3") (pintype "passive"))
      (node (ref "SR3") (pin "3") (pinfunction "3_3") (pintype "passive"))
      (node (ref "SR5") (pin "3") (pinfunction "3_3") (pintype "passive"))
      (node (ref "SR7") (pin "3") (pinfunction "3_3") (pintype "passive"))
      (node (ref "SR9") (pin "3") (pinfunction "3_3") (pintype "passive"))
    )
    (net (code "13") (name "/0_12") (class "Default")
      (node (ref "P0") (pin "13") (pinfunction "13_13") (pintype "passive"))
      (node (ref "SR1") (pin "4") (pinfunction "4_4") (pintype "passive"))
    )
    (net (code "14") (name "/0_NC0") (class "Default")
      (node (ref "P0") (pin "14") (pinfunction "14_14") (pintype "passive"))
      (node (ref "SR1") (pin "5") (pinfunction "5_5") (pintype "passive"))
    )
    (net (code "15") (name "/0_NC1") (class "Default")
      (node (ref "P0") (pin "15") (pinfunction "15_15") (pintype "passive"))
      (node (ref "SR1") (pin "6") (pinfunction "6_6") (pintype "passive"))
    )
    (net (code "16") (name "/0_NC2") (class "Default")
      (node (ref "P0") (pin "16") (pinfunction "16_16") (pintype "passive"))
      (node (ref "SR1") (pin "7") (pinfunction "7_7") (pintype "passive"))
    )
    (net (code "17") (name "/1_00") (class "Default")
      (node (ref "P1") (pin "1") (pinfunction "1_1") (pintype "passive"))
      (node (ref "SR2") (pin "15") (pinfunction "15_15") (pintype "passive"))
    )
    (net (code "18") (name "/1_01") (class "Default")
      (node (ref "P1") (pin "2") (pinfunction "2_2") (pintype "passive"))
      (node (ref "SR2") (pin "1") (pinfunction "1_1") (pintype "passive"))
    )
    (net (code "19") (name "/1_02") (class "Default")
      (node (ref "P1") (pin "3") (pinfunction "3_3") (pintype "passive"))
      (node (ref "SR2") (pin "2") (pinfunction "2_2") (pintype "passive"))
    )
    (net (code "20") (name "/1_03") (class "Default")
      (node (ref "P1") (pin "4") (pinfunction "4_4") (pintype "passive"))
      (node (ref "SR2") (pin "3") (pinfunction "3_3") (pintype "passive"))
    )
    (net (code "21") (name "/1_04") (class "Default")
      (node (ref "P1") (pin "5") (pinfunction "5_5") (pintype "passive"))
      (node (ref "SR2") (pin "4") (pinfunction "4_4") (pintype "passive"))
    )
    (net (code "22") (name "/1_05") (class "Default")
      (node (ref "P1") (pin "6") (pinfunction "6_6") (pintype "passive"))
      (node (ref "SR2") (pin "5") (pinfunction "5_5") (pintype "passive"))
    )
    (net (code "23") (name "/1_06") (class "Default")
      (node (ref "P1") (pin "7") (pinfunction "7_7") (pintype "passive"))
      (node (ref "SR2") (pin "6") (pinfunction "6_6") (pintype "passive"))
    )
    (net (code "24") (name "/1_07") (class "Default")
      (node (ref "P1") (pin "8") (pinfunction "8_8") (pintype "passive"))
      (node (ref "SR2") (pin "7") (pinfunction "7_7") (pintype "passive"))
    )
    (net (code "25") (name "/1_08") (class "Default")
      (node (ref "P1") (pin "9") (pinfunction "9_9") (pintype "passive"))
      (node (ref "SR3") (pin "15") (pinfunction "15_15") (pintype "passive"))
    )
    (net (code "26") (name "/1_09") (class "Default")
      (node (ref "P1") (pin "10") (pinfunction "10_10") (pintype "passive"))
      (node (ref "SR3") (pin "1") (pinfunction "1_1") (pintype "passive"))
    )
    (net (code "27") (name "/1_10") (class "Default")
      (node (ref "P1") (pin "11") (pinfunction "11_11") (pintype "passive"))
      (node (ref "SR3") (pin "2") (pinfunction "2_2") (pintype "passive"))
    )
    (net (code "28") (name "/1_12") (class "Default")
      (node (ref "P1") (pin "13") (pinfunction "13_13") (pintype "passive"))
      (node (ref "SR3") (pin "4") (pinfunction "4_4") (pintype "passive"))
    )
    (net (code "29") (name "/1_NC0") (class "Default")
      (node (ref "P1") (pin "14") (pinfunction "14_14") (pintype "passive"))
      (node (ref "SR3") (pin "5") (pinfunction "5_5") (pintype "passive"))
    )
    (net (code "30") (name "/1_NC1") (class "Default")
      (node (ref "P1") (pin "15") (pinfunction "15_15") (pintype "passive"))
      (node (ref "SR3") (pin "6") (pinfunction "6_6") (pintype "passive"))
    )
    (net (code "31") (name "/1_NC2") (class "Default")
      (node (ref "P1") (pin "16") (pinfunction "16_16") (pintype "passive"))
      (node (ref "SR3") (pin "7") (pinfunction "7_7") (pintype "passive"))
    )
    (net (code "32") (name "/2_00") (class "Default")
      (node (ref "P2") (pin "1") (pinfunction "1_1") (pintype "passive"))
      (node (ref "SR4") (pin "15") (pinfunction "15_15") (pintype "passive"))
    )
    (net (code "33") (name "/2_01") (class "Default")
      (node (ref "P2") (pin "2") (pinfunction "2_2") (pintype "passive"))
      (node (ref "SR4") (pin "1") (pinfunction "1_1") (pintype "passive"))
    )
    (net (code "34") (name "/2_02") (class "Default")
      (node (ref "P2") (pin "3") (pinfunction "3_3") (pintype "passive"))
      (node (ref "SR4") (pin "2") (pinfunction "2_2") (pintype "passive"))
    )
    (net (code "35") (name "/2_03") (class "Default")
      (node (ref "P2") (pin "4") (pinfunction "4_4") (pintype "passive"))
      (node (ref "SR4") (pin "3") (pinfunction "3_3") (pintype "passive"))
    )
    (net (code "36") (name "/2_04") (class "Default")
      (node (ref "P2") (pin "5") (pinfunction "5_5") (pintype "passive"))
      (node (ref "SR4") (pin "4") (pinfunction "4_4") (pintype "passive"))
    )
    (net (code "37") (name "/2_05") (class "Default")
      (node (ref "P2") (pin "6") (pinfunction "6_6") (pintype "passive"))
      (node (ref "SR4") (pin "5") (pinfunction "5_5") (pintype "passive"))
    )
    (net (code "38") (name "/2_06") (class "Default")
      (node (ref "P2") (pin "7") (pinfunction "7_7") (pintype "passive"))
      (node (ref "SR4") (pin "6") (pinfunction "6_6") (pintype "passive"))
    )
    (net (code "39") (name "/2_07") (class "Default")
      (node (ref "P2") (pin "8") (pinfunction "8_8") (pintype "passive"))
      (node (ref "SR4") (pin "7") (pinfunction "7_7") (pintype "passive"))
    )
    (net (code "40") (name "/2_08") (class "Default")
      (node (ref "P2") (pin "9") (pinfunction "9_9") (pintype "passive"))
      (node (ref "SR5") (pin "15") (pinfunction "15_15") (pintype "passive"))
    )
    (net (code "41") (name "/2_09") (class "Default")
      (node (ref "P2") (pin "10") (pinfunction "10_10") (pintype "passive"))
      (node (ref "SR5") (pin "1") (pinfunction "1_1") (pintype "passive"))
    )
    (net (code "42") (name "/2_10") (class "Default")
      (node (ref "P2") (pin "11") (pinfunction "11_11") (pintype "passive"))
      (node (ref "SR5") (pin "2") (pinfunction "2_2") (pintype "passive"))
    )
    (net (code "43") (name "/2_12") (class "Default")
      (node (ref "P2") (pin "13") (pinfunction "13_13") (pintype "passive"))
      (node (ref "SR5") (pin "4") (pinfunction "4_4") (pintype "passive"))
    )
    (net (code "44") (name "/2_NC0") (class "Default")
      (node (ref "P2") (pin "14") (pinfunction "14_14") (pintype "passive"))
      (node (ref "SR5") (pin "5") (pinfunction "5_5") (pintype "passive"))
    )
    (net (code "45") (name "/2_NC1") (class "Default")
      (node (ref "P2") (pin "15") (pinfunction "15_15") (pintype "passive"))
      (node (ref "SR5") (pin "6") (pinfunction "6_6") (pintype "passive"))
    )
    (net (code "46") (name "/2_NC2") (class "Default")
      (node (ref "P2") (pin "16") (pinfunction "16_16") (pintype "passive"))
      (node (ref "SR5") (pin "7") (pinfunction "7_7") (pintype "passive"))
    )
    (net (code "47") (name "/3_00") (class "Default")
      (node (ref "P3") (pin "1") (pinfunction "1_1") (pintype "passive"))
      (node (ref "SR6") (pin "15") (pinfunction "15_15") (pintype "passive"))
    )
    (net (code "48") (name "/3_01") (class "Default")
      (node (ref "P3") (pin "2") (pinfunction "2_2") (pintype "passive"))
      (node (ref "SR6") (pin "1") (pinfunction "1_1") (pintype "passive"))
    )
    (net (code "49") (name "/3_02") (class "Default")
      (node (ref "P3") (pin "3") (pinfunction "3_3") (pintype "passive"))
      (node (ref "SR6") (pin "2") (pinfunction "2_2") (pintype "passive"))
    )
    (net (code "50") (name "/3_03") (class "Default")
      (node (ref "P3") (pin "4") (pinfunction "4_4") (pintype "passive"))
      (node (ref "SR6") (pin "3") (pinfunction "3_3") (pintype "passive"))
    )
    (net (code "51") (name "/3_04") (class "Default")
      (node (ref "P3") (pin "5") (pinfunction "5_5") (pintype "passive"))
      (node (ref "SR6") (pin "4") (pinfunction "4_4") (pintype "passive"))
    )
    (net (code "52") (name "/3_05") (class "Default")
      (node (ref "P3") (pin "6") (pinfunction "6_6") (pintype "passive"))
      (node (ref "SR6") (pin "5") (pinfunction "5_5") (pintype "passive"))
    )
    (net (code "53") (name "/3_06") (class "Default")
      (node (ref "P3") (pin "7") (pinfunction "7_7") (pintype "passive"))
      (node (ref "SR6") (pin "6") (pinfunction "6_6") (pintype "passive"))
    )
    (net (code "54") (name "/3_07") (class "Default")
      (node (ref "P3") (pin "8") (pinfunction "8_8") (pintype "passive"))
      (node (ref "SR6") (pin "7") (pinfunction "7_7") (pintype "passive"))
    )
    (net (code "55") (name "/3_08") (class "Default")
      (node (ref "P3") (pin "9") (pinfunction "9_9") (pintype "passive"))
      (node (ref "SR7") (pin "15") (pinfunction "15_15") (pintype "passive"))
    )
    (net (code "56") (name "/3_09") (class "Default")
      (node (ref "P3") (pin "10") (pinfunction "10_10") (pintype "passive"))
      (node (ref "SR7") (pin "1") (pinfunction "1_1") (pintype "passive"))
    )
    (net (code "57") (name "/3_10") (class "Default")
      (node (ref "P3") (pin "11") (pinfunction "11_11") (pintype "passive"))
      (node (ref "SR7") (pin "2") (pinfunction "2_2") (pintype "passive"))
    )
    (net (code "58") (name "/3_12") (class "Default")
      (node (ref "P3") (pin "13") (pinfunction "13_13") (pintype "passive"))
      (node (ref "SR7") (pin "4") (pinfunction "4_4") (pintype "passive"))
    )
    (net (code "59") (name "/3_NC0") (class "Default")
      (node (ref "P3") (pin "14") (pinfunction "14_14") (pintype "passive"))
      (node (ref "SR7") (pin "5") (pinfunction "5_5") (pintype "passive"))
    )
    (net (code "60") (name "/3_NC1") (class "Default")
      (node (ref "P3") (pin "15") (pinfunction "15_15") (pintype "passive"))
      (node (ref "SR7") (pin "6") (pinfunction "6_6") (pintype "passive"))
    )
    (net (code "61") (name "/3_NC2") (class "Default")
      (node (ref "P3") (pin "16") (pinfunction "16_16") (pintype "passive"))
      (node (ref "SR7") (pin "7") (pinfunction "7_7") (pintype "passive"))
    )
    (net (code "62") (name "/4_00") (class "Default")
      (node (ref "P4") (pin "1") (pinfunction "1_1") (pintype "passive"))
      (node (ref "SR8") (pin "15") (pinfunction "15_15") (pintype "passive"))
    )
    (net (code "63") (name "/4_01") (class "Default")
      (node (ref "P4") (pin "2") (pinfunction "2_2") (pintype "passive"))
      (node (ref "SR8") (pin "1") (pinfunction "1_1") (pintype "passive"))
    )
    (net (code "64") (name "/4_02") (class "Default")
      (node (ref "P4") (pin "3") (pinfunction "3_3") (pintype "passive"))
      (node (ref "SR8") (pin "2") (pinfunction "2_2") (pintype "passive"))
    )
    (net (code "65") (name "/4_03") (class "Default")
      (node (ref "P4") (pin "4") (pinfunction "4_4") (pintype "passive"))
      (node (ref "SR8") (pin "3") (pinfunction "3_3") (pintype "passive"))
    )
    (net (code "66") (name "/4_04") (class "Default")
      (node (ref "P4") (pin "5") (pinfunction "5_5") (pintype "passive"))
      (node (ref "SR8") (pin "4") (pinfunction "4_4") (pintype "passive"))
    )
    (net (code "67") (name "/4_05") (class "Default")
      (node (ref "P4") (pin "6") (pinfunction "6_6") (pintype "passive"))
      (node (ref "SR8") (pin "5") (pinfunction "5_5") (pintype "passive"))
    )
    (net (code "68") (name "/4_06") (class "Default")
      (node (ref "P4") (pin "7") (pinfunction "7_7") (pintype "passive"))
      (node (ref "SR8") (pin "6") (pinfunction "6_6") (pintype "passive"))
    )
    (net (code "69") (name "/4_07") (class "Default")
      (node (ref "P4") (pin "8") (pinfunction "8_8") (pintype "passive"))
      (node (ref "SR8") (pin "7") (pinfunction "7_7") (pintype "passive"))
    )
    (net (code "70") (name "/4_08") (class "Default")
      (node (ref "P4") (pin "9") (pinfunction "9_9") (pintype "passive"))
      (node (ref "SR9") (pin "15") (pinfunction "15_15") (pintype "passive"))
    )
    (net (code "71") (name "/4_09") (class "Default")
      (node (ref "P4") (pin "10") (pinfunction "10_10") (pintype "passive"))
      (node (ref "SR9") (pin "1") (pinfunction "1_1") (pintype "passive"))
    )
    (net (code "72") (name "/4_10") (class "Default")
      (node (ref "P4") (pin "11") (pinfunction "11_11") (pintype "passive"))
      (node (ref "SR9") (pin "2") (pinfunction "2_2") (pintype "passive"))
    )
    (net (code "73") (name "/4_12") (class "Default")
      (node (ref "P4") (pin "13") (pinfunction "13_13") (pintype "passive"))
      (node (ref "SR9") (pin "4") (pinfunction "4_4") (pintype "passive"))
    )
    (net (code "74") (name "/4_NC0") (class "Default")
      (node (ref "P4") (pin "14") (pinfunction "14_14") (pintype "passive"))
      (node (ref "SR9") (pin "5") (pinfunction "5_5") (pintype "passive"))
    )
    (net (code "75") (name "/4_NC1") (class "Default")
      (node (ref "P4") (pin "15") (pinfunction "15_15") (pintype "passive"))
      (node (ref "SR9") (pin "6") (pinfunction "6_6") (pintype "passive"))
    )
    (net (code "76") (name "/4_NC2") (class "Default")
      (node (ref "P4") (pin "16") (pinfunction "16_16") (pintype "passive"))
      (node (ref "SR9") (pin "7") (pinfunction "7_7") (pintype "passive"))
    )
    (net (code "77") (name "/5_00") (class "Default")
      (node (ref "P5") (pin "1") (pinfunction "1_1") (pintype "passive"))
      (node (ref "SR10") (pin "15") (pinfunction "15_15") (pintype "passive"))
    )
    (net (code "78") (name "/5_01") (class "Default")
      (node (ref "P5") (pin "2") (pinfunction "2_2") (pintype "passive"))
      (node (ref "SR10") (pin "1") (pinfunction "1_1") (pintype "passive"))
    )
    (net (code "79") (name "/5_02") (class "Default")
      (node (ref "P5") (pin "3") (pinfunction "3_3") (pintype "passive"))
      (node (ref "SR10") (pin "2") (pinfunction "2_2") (pintype "passive"))
    )
    (net (code "80") (name "/5_03") (class "Default")
      (node (ref "P5") (pin "4") (pinfunction "4_4") (pintype "passive"))
      (node (ref "SR10") (pin "3") (pinfunction "3_3") (pintype "passive"))
    )
    (net (code "81") (name "/5_04") (class "Default")
      (node (ref "P5") (pin "5") (pinfunction "5_5") (pintype "passive"))
      (node (ref "SR10") (pin "4") (pinfunction "4_4") (pintype "passive"))
    )
    (net (code "82") (name "/5_05") (class "Default")
      (node (ref "P5") (pin "6") (pinfunction "6_6") (pintype "passive"))
      (node (ref "SR10") (pin "5") (pinfunction "5_5") (pintype "passive"))
    )
    (net (code "83") (name "/5_06") (class "Default")
      (node (ref "P5") (pin "7") (pinfunction "7_7") (pintype "passive"))
      (node (ref "SR10") (pin "6") (pinfunction "6_6") (pintype "passive"))
    )
    (net (code "84") (name "/5_07") (class "Default")
      (node (ref "P5") (pin "8") (pinfunction "8_8") (pintype "passive"))
      (node (ref "SR10") (pin "7") (pinfunction "7_7") (pintype "passive"))
    )
    (net (code "85") (name "/5_08") (class "Default")
      (node (ref "P5") (pin "9") (pinfunction "9_9") (pintype "passive"))
      (node (ref "SR11") (pin "15") (pinfunction "15_15") (pintype "passive"))
    )
    (net (code "86") (name "/5_09") (class "Default")
      (node (ref "P5") (pin "10") (pinfunction "10_10") (pintype "passive"))
      (node (ref "SR11") (pin "1") (pinfunction "1_1") (pintype "passive"))
    )
    (net (code "87") (name "/5_10") (class "Default")
      (node (ref "P5") (pin "11") (pinfunction "11_11") (pintype "passive"))
      (node (ref "SR11") (pin "2") (pinfunction "2_2") (pintype "passive"))
    )
    (net (code "88") (name "/5_12") (class "Default")
      (node (ref "P5") (pin "13") (pinfunction "13_13") (pintype "passive"))
      (node (ref "SR11") (pin "4") (pinfunction "4_4") (pintype "passive"))
    )
    (net (code "89") (name "/5_NC0") (class "Default")
      (node (ref "P5") (pin "14") (pinfunction "14_14") (pintype "passive"))
      (node (ref "SR11") (pin "5") (pinfunction "5_5") (pintype "passive"))
    )
    (net (code "90") (name "/5_NC1") (class "Default")
      (node (ref "P5") (pin "15") (pinfunction "15_15") (pintype "passive"))
      (node (ref "SR11") (pin "6") (pinfunction "6_6") (pintype "passive"))
    )
    (net (code "91") (name "/5_NC2") (class "Default")
      (node (ref "P5") (pin "16") (pinfunction "16_16") (pintype "passive"))
      (node (ref "SR11") (pin "7") (pinfunction "7_7") (pintype "passive"))
    )
    (net (code "92") (name "/6_00") (class "Default")
      (node (ref "P6") (pin "1") (pinfunction "1_1") (pintype "passive"))
      (node (ref "SR12") (pin "15") (pinfunction "15_15") (pintype "passive"))
    )
    (net (code "93") (name "/6_01") (class "Default")
      (node (ref "P6") (pin "2") (pinfunction "2_2") (pintype "passive"))
      (node (ref "SR12") (pin "1") (pinfunction "1_1") (pintype "passive"))
    )
    (net (code "94") (name "/6_02") (class "Default")
      (node (ref "P6") (pin "3") (pinfunction "3_3") (pintype "passive"))
      (node (ref "SR12") (pin "2") (pinfunction "2_2") (pintype "passive"))
    )
    (net (code "95") (name "/6_03") (class "Default")
      (node (ref "P6") (pin "4") (pinfunction "4_4") (pintype "passive"))
      (node (ref "SR12") (pin "3") (pinfunction "3_3") (pintype "passive"))
    )
    (net (code "96") (name "/6_04") (class "Default")
      (node (ref "P6") (pin "5") (pinfunction "5_5") (pintype "passive"))
      (node (ref "SR12") (pin "4") (pinfunction "4_4") (pintype "passive"))
    )
    (net (code "97") (name "/6_05") (class "Default")
      (node (ref "P6") (pin "6") (pinfunction "6_6") (pintype "passive"))
      (node (ref "SR12") (pin "5") (pinfunction "5_5") (pintype "passive"))
    )
    (net (code "98") (name "/6_06") (class "Default")
      (node (ref "P6") (pin "7") (pinfunction "7_7") (pintype "passive"))
      (node (ref "SR12") (pin "6") (pinfunction "6_6") (pintype "passive"))
    )
    (net (code "99") (name "/6_07") (class "Default")
      (node (ref "P6") (pin "8") (pinfunction "8_8") (pintype "passive"))
      (node (ref "SR12") (pin "7") (pinfunction "7_7") (pintype "passive"))
    )
    (net (code "100") (name "/6_08") (class "Default")
      (node (ref "P6") (pin "9") (pinfunction "9_9") (pintype "passive"))
      (node (ref "SR13") (pin "15") (pinfunction "15_15") (pintype "passive"))
    )
    (net (code "101") (name "/6_09") (class "Default")
      (node (ref "P6") (pin "10") (pinfunction "10_10") (pintype "passive"))
      (node (ref "SR13") (pin "1") (pinfunction "1_1") (pintype "passive"))
    )
    (net (code "102") (name "/6_10") (class "Default")
      (node (ref "P6") (pin "11") (pinfunction "11_11") (pintype "passive"))
      (node (ref "SR13") (pin "2") (pinfunction "2_2") (pintype "passive"))
    )
    (net (code "103") (name "/6_12") (class "Default")
      (node (ref "P6") (pin "13") (pinfunction "13_13") (pintype "passive"))
      (node (ref "SR13") (pin "4") (pinfunction "4_4") (pintype "passive"))
    )
    (net (code "104") (name "/6_NC0") (class "Default")
      (node (ref "P6") (pin "14") (pinfunction "14_14") (pintype "passive"))
      (node (ref "SR13") (pin "5") (pinfunction "5_5") (pintype "passive"))
    )
    (net (code "105") (name "/6_NC1") (class "Default")
      (node (ref "P6") (pin "15") (pinfunction "15_15") (pintype "passive"))
      (node (ref "SR13") (pin "6") (pinfunction "6_6") (pintype "passive"))
    )
    (net (code "106") (name "/6_NC2") (class "Default")
      (node (ref "P6") (pin "16") (pinfunction "16_16") (pintype "passive"))
      (node (ref "SR13") (pin "7") (pinfunction "7_7") (pintype "passive"))
    )
    (net (code "107") (name "/7_00") (class "Default")
      (node (ref "SR14") (pin "15") (pinfunction "15_15") (pintype "passive"))
    )
    (net (code "108") (name "/7_01") (class "Default")
      (node (ref "P7") (pin "2") (pinfunction "2_2") (pintype "passive"))
      (node (ref "SR14") (pin "1") (pinfunction "1_1") (pintype "passive"))
    )
    (net (code "109") (name "/7_02") (class "Default")
      (node (ref "P7") (pin "3") (pinfunction "3_3") (pintype "passive"))
      (node (ref "SR14") (pin "2") (pinfunction "2_2") (pintype "passive"))
    )
    (net (code "110") (name "/7_03") (class "Default")
      (node (ref "P7") (pin "4") (pinfunction "4_4") (pintype "passive"))
      (node (ref "SR14") (pin "3") (pinfunction "3_3") (pintype "passive"))
    )
    (net (code "111") (name "/7_04") (class "Default")
      (node (ref "P7") (pin "5") (pinfunction "5_5") (pintype "passive"))
      (node (ref "SR14") (pin "4") (pinfunction "4_4") (pintype "passive"))
    )
    (net (code "112") (name "/7_05") (class "Default")
      (node (ref "P7") (pin "6") (pinfunction "6_6") (pintype "passive"))
      (node (ref "SR14") (pin "5") (pinfunction "5_5") (pintype "passive"))
    )
    (net (code "113") (name "/7_06") (class "Default")
      (node (ref "P7") (pin "7") (pinfunction "7_7") (pintype "passive"))
      (node (ref "SR14") (pin "6") (pinfunction "6_6") (pintype "passive"))
    )
    (net (code "114") (name "/7_07") (class "Default")
      (node (ref "P7") (pin "8") (pinfunction "8_8") (pintype "passive"))
      (node (ref "SR14") (pin "7") (pinfunction "7_7") (pintype "passive"))
    )
    (net (code "115") (name "/7_08") (class "Default")
      (node (ref "P7") (pin "9") (pinfunction "9_9") (pintype "passive"))
      (node (ref "SR15") (pin "15") (pinfunction "15_15") (pintype "passive"))
    )
    (net (code "116") (name "/7_09") (class "Default")
      (node (ref "P7") (pin "10") (pinfunction "10_10") (pintype "passive"))
      (node (ref "SR15") (pin "1") (pinfunction "1_1") (pintype "passive"))
    )
    (net (code "117") (name "/7_10") (class "Default")
      (node (ref "P7") (pin "11") (pinfunction "11_11") (pintype "passive"))
      (node (ref "SR15") (pin "2") (pinfunction "2_2") (pintype "passive"))
    )
    (net (code "118") (name "/7_11") (class "Default")
      (node (ref "P7") (pin "12") (pinfunction "12_12") (pintype "passive"))
      (node (ref "SR15") (pin "3") (pinfunction "3_3") (pintype "passive"))
    )
    (net (code "119") (name "/7_12") (class "Default")
      (node (ref "P7") (pin "13") (pinfunction "13_13") (pintype "passive"))
      (node (ref "SR15") (pin "4") (pinfunction "4_4") (pintype "passive"))
    )
    (net (code "120") (name "/7_NC0") (class "Default")
      (node (ref "P7") (pin "14") (pinfunction "14_14") (pintype "passive"))
      (node (ref "SR15") (pin "5") (pinfunction "5_5") (pintype "passive"))
    )
    (net (code "121") (name "/7_NC1") (class "Default")
      (node (ref "P7") (pin "15") (pinfunction "15_15") (pintype "passive"))
      (node (ref "SR15") (pin "6") (pinfunction "6_6") (pintype "passive"))
    )
    (net (code "122") (name "/7_NC2") (class "Default")
      (node (ref "P7") (pin "16") (pinfunction "16_16") (pintype "passive"))
      (node (ref "SR15") (pin "7") (pinfunction "7_7") (pintype "passive"))
    )
    (net (code "123") (name "/8_00") (class "Default")
      (node (ref "P8") (pin "1") (pinfunction "1_1") (pintype "passive"))
      (node (ref "SR16") (pin "15") (pinfunction "15_15") (pintype "passive"))
    )
    (net (code "124") (name "/8_01") (class "Default")
      (node (ref "P8") (pin "2") (pinfunction "2_2") (pintype "passive"))
      (node (ref "SR16") (pin "1") (pinfunction "1_1") (pintype "passive"))
    )
    (net (code "125") (name "/8_02") (class "Default")
      (node (ref "P8") (pin "3") (pinfunction "3_3") (pintype "passive"))
      (node (ref "SR16") (pin "2") (pinfunction "2_2") (pintype "passive"))
    )
    (net (code "126") (name "/8_03") (class "Default")
      (node (ref "P8") (pin "4") (pinfunction "4_4") (pintype "passive"))
      (node (ref "SR16") (pin "3") (pinfunction "3_3") (pintype "passive"))
    )
    (net (code "127") (name "/8_04") (class "Default")
      (node (ref "P8") (pin "5") (pinfunction "5_5") (pintype "passive"))
      (node (ref "SR16") (pin "4") (pinfunction "4_4") (pintype "passive"))
    )
    (net (code "128") (name "/8_05") (class "Default")
      (node (ref "P8") (pin "6") (pinfunction "6_6") (pintype "passive"))
      (node (ref "SR16") (pin "5") (pinfunction "5_5") (pintype "passive"))
    )
    (net (code "129") (name "/8_06") (class "Default")
      (node (ref "P8") (pin "7") (pinfunction "7_7") (pintype "passive"))
      (node (ref "SR16") (pin "6") (pinfunction "6_6") (pintype "passive"))
    )
    (net (code "130") (name "/8_07") (class "Default")
      (node (ref "P8") (pin "8") (pinfunction "8_8") (pintype "passive"))
      (node (ref "SR16") (pin "7") (pinfunction "7_7") (pintype "passive"))
    )
    (net (code "131") (name "/8_08") (class "Default")
      (node (ref "P8") (pin "9") (pinfunction "9_9") (pintype "passive"))
      (node (ref "SR17") (pin "15") (pinfunction "15_15") (pintype "passive"))
    )
    (net (code "132") (name "/8_09") (class "Default")
      (node (ref "P8") (pin "10") (pinfunction "10_10") (pintype "passive"))
      (node (ref "SR17") (pin "1") (pinfunction "1_1") (pintype "passive"))
    )
    (net (code "133") (name "/8_10") (class "Default")
      (node (ref "P8") (pin "11") (pinfunction "11_11") (pintype "passive"))
      (node (ref "SR17") (pin "2") (pinfunction "2_2") (pintype "passive"))
    )
    (net (code "134") (name "/8_11") (class "Default")
      (node (ref "P8") (pin "12") (pinfunction "12_12") (pintype "passive"))
      (node (ref "SR17") (pin "3") (pinfunction "3_3") (pintype "passive"))
    )
    (net (code "135") (name "/8_12") (class "Default")
      (node (ref "P8") (pin "13") (pinfunction "13_13") (pintype "passive"))
      (node (ref "SR17") (pin "4") (pinfunction "4_4") (pintype "passive"))
    )
    (net (code "136") (name "/8_NC0") (class "Default")
      (node (ref "P8") (pin "14") (pinfunction "14_14") (pintype "passive"))
      (node (ref "SR17") (pin "5") (pinfunction "5_5") (pintype "passive"))
    )
    (net (code "137") (name "/8_NC1") (class "Default")
      (node (ref "P8") (pin "15") (pinfunction "15_15") (pintype "passive"))
      (node (ref "SR17") (pin "6") (pinfunction "6_6") (pintype "passive"))
    )
    (net (code "138") (name "/8_NC2") (class "Default")
      (node (ref "P8") (pin "16") (pinfunction "16_16") (pintype "passive"))
      (node (ref "SR17") (pin "7") (pinfunction "7_7") (pintype "passive"))
    )
    (net (code "139") (name "/9-12") (class "Default")
      (node (ref "P9") (pin "13") (pinfunction "13_13") (pintype "passive"))
    )
    (net (code "140") (name "/9_00") (class "Default")
      (node (ref "P9") (pin "1") (pinfunction "1_1") (pintype "passive"))
      (node (ref "SR18") (pin "15") (pinfunction "15_15") (pintype "passive"))
    )
    (net (code "141") (name "/9_01") (class "Default")
      (node (ref "P9") (pin "2") (pinfunction "2_2") (pintype "passive"))
      (node (ref "SR18") (pin "1") (pinfunction "1_1") (pintype "passive"))
    )
    (net (code "142") (name "/9_02") (class "Default")
      (node (ref "P9") (pin "3") (pinfunction "3_3") (pintype "passive"))
      (node (ref "SR18") (pin "2") (pinfunction "2_2") (pintype "passive"))
    )
    (net (code "143") (name "/9_03") (class "Default")
      (node (ref "P9") (pin "4") (pinfunction "4_4") (pintype "passive"))
      (node (ref "SR18") (pin "3") (pinfunction "3_3") (pintype "passive"))
    )
    (net (code "144") (name "/9_04") (class "Default")
      (node (ref "P9") (pin "5") (pinfunction "5_5") (pintype "passive"))
      (node (ref "SR18") (pin "4") (pinfunction "4_4") (pintype "passive"))
    )
    (net (code "145") (name "/9_05") (class "Default")
      (node (ref "P9") (pin "6") (pinfunction "6_6") (pintype "passive"))
      (node (ref "SR18") (pin "5") (pinfunction "5_5") (pintype "passive"))
    )
    (net (code "146") (name "/9_06") (class "Default")
      (node (ref "P9") (pin "7") (pinfunction "7_7") (pintype "passive"))
      (node (ref "SR18") (pin "6") (pinfunction "6_6") (pintype "passive"))
    )
    (net (code "147") (name "/9_07") (class "Default")
      (node (ref "P9") (pin "8") (pinfunction "8_8") (pintype "passive"))
      (node (ref "SR18") (pin "7") (pinfunction "7_7") (pintype "passive"))
    )
    (net (code "148") (name "/9_08") (class "Default")
      (node (ref "P9") (pin "9") (pinfunction "9_9") (pintype "passive"))
      (node (ref "SR19") (pin "15") (pinfunction "15_15") (pintype "passive"))
    )
    (net (code "149") (name "/9_09") (class "Default")
      (node (ref "P9") (pin "10") (pinfunction "10_10") (pintype "passive"))
      (node (ref "SR19") (pin "1") (pinfunction "1_1") (pintype "passive"))
    )
    (net (code "150") (name "/9_10") (class "Default")
      (node (ref "P9") (pin "11") (pinfunction "11_11") (pintype "passive"))
      (node (ref "SR19") (pin "2") (pinfunction "2_2") (pintype "passive"))
    )
    (net (code "151") (name "/9_12") (class "Default")
      (node (ref "SR19") (pin "4") (pinfunction "4_4") (pintype "passive"))
    )
    (net (code "152") (name "/9_NC0") (class "Default")
      (node (ref "P9") (pin "14") (pinfunction "14_14") (pintype "passive"))
      (node (ref "SR19") (pin "5") (pinfunction "5_5") (pintype "passive"))
    )
    (net (code "153") (name "/9_NC1") (class "Default")
      (node (ref "P9") (pin "15") (pinfunction "15_15") (pintype "passive"))
      (node (ref "SR19") (pin "6") (pinfunction "6_6") (pintype "passive"))
    )
    (net (code "154") (name "/9_NC2") (class "Default")
      (node (ref "P9") (pin "16") (pinfunction "16_16") (pintype "passive"))
      (node (ref "SR19") (pin "7") (pinfunction "7_7") (pintype "passive"))
    )
    (net (code "155") (name "/37_00") (class "Default")
      (node (ref "P7") (pin "1") (pinfunction "1_1") (pintype "passive"))
    )
    (net (code "156") (name "/DS_8") (class "Default")
      (node (ref "P10") (pin "3") (pinfunction "3_3") (pintype "passive"))
      (node (ref "SR0") (pin "14") (pinfunction "14_14") (pintype "passive"))
    )
    (net (code "157") (name "/DriverPin1") (class "Default")
      (node (ref "J23") (pin "2") (pinfunction "2_2") (pintype "passive"))
      (node (ref "J24") (pin "2") (pinfunction "2_2") (pintype "passive"))
      (node (ref "J25") (pin "2") (pinfunction "2_2") (pintype "passive"))
      (node (ref "J26") (pin "2") (pinfunction "2_2") (pintype "passive"))
      (node (ref "J27") (pin "2") (pinfunction "2_2") (pintype "passive"))
      (node (ref "J28") (pin "2") (pinfunction "2_2") (pintype "passive"))
      (node (ref "J29") (pin "2") (pinfunction "2_2") (pintype "passive"))
      (node (ref "J30") (pin "2") (pinfunction "2_2") (pintype "passive"))
      (node (ref "J31") (pin "2") (pinfunction "2_2") (pintype "passive"))
      (node (ref "J32") (pin "2") (pinfunction "2_2") (pintype "passive"))
      (node (ref "J33") (pin "2") (pinfunction "2_2") (pintype "passive"))
    )
    (net (code "158") (name "/DriverPin2") (class "Default")
      (node (ref "J23") (pin "1") (pinfunction "1_1") (pintype "passive"))
      (node (ref "J24") (pin "1") (pinfunction "1_1") (pintype "passive"))
      (node (ref "J25") (pin "1") (pinfunction "1_1") (pintype "passive"))
      (node (ref "J26") (pin "1") (pinfunction "1_1") (pintype "passive"))
      (node (ref "J27") (pin "1") (pinfunction "1_1") (pintype "passive"))
      (node (ref "J28") (pin "1") (pinfunction "1_1") (pintype "passive"))
      (node (ref "J29") (pin "1") (pinfunction "1_1") (pintype "passive"))
      (node (ref "J30") (pin "1") (pinfunction "1_1") (pintype "passive"))
      (node (ref "J31") (pin "1") (pinfunction "1_1") (pintype "passive"))
      (node (ref "J32") (pin "1") (pinfunction "1_1") (pintype "passive"))
      (node (ref "J33") (pin "1") (pinfunction "1_1") (pintype "passive"))
    )
    (net (code "159") (name "/SH_CP_11") (class "Default")
      (node (ref "P10") (pin "5") (pinfunction "5_5") (pintype "passive"))
      (node (ref "SR0") (pin "11") (pinfunction "11_11") (pintype "passive"))
      (node (ref "SR1") (pin "11") (pinfunction "11_11") (pintype "passive"))
      (node (ref "SR10") (pin "11") (pinfunction "11_11") (pintype "passive"))
      (node (ref "SR11") (pin "11") (pinfunction "11_11") (pintype "passive"))
      (node (ref "SR12") (pin "11") (pinfunction "11_11") (pintype "passive"))
      (node (ref "SR13") (pin "11") (pinfunction "11_11") (pintype "passive"))
      (node (ref "SR14") (pin "11") (pinfunction "11_11") (pintype "passive"))
      (node (ref "SR15") (pin "11") (pinfunction "11_11") (pintype "passive"))
      (node (ref "SR16") (pin "11") (pinfunction "11_11") (pintype "passive"))
      (node (ref "SR17") (pin "11") (pinfunction "11_11") (pintype "passive"))
      (node (ref "SR18") (pin "11") (pinfunction "11_11") (pintype "passive"))
      (node (ref "SR19") (pin "11") (pinfunction "11_11") (pintype "passive"))
      (node (ref "SR2") (pin "11") (pinfunction "11_11") (pintype "passive"))
      (node (ref "SR3") (pin "11") (pinfunction "11_11") (pintype "passive"))
      (node (ref "SR4") (pin "11") (pinfunction "11_11") (pintype "passive"))
      (node (ref "SR5") (pin "11") (pinfunction "11_11") (pintype "passive"))
      (node (ref "SR6") (pin "11") (pinfunction "11_11") (pintype "passive"))
      (node (ref "SR7") (pin "11") (pinfunction "11_11") (pintype "passive"))
      (node (ref "SR8") (pin "11") (pinfunction "11_11") (pintype "passive"))
      (node (ref "SR9") (pin "11") (pinfunction "11_11") (pintype "passive"))
    )
    (net (code "160") (name "/ST_CP_10") (class "Default")
      (node (ref "P10") (pin "4") (pinfunction "4_4") (pintype "passive"))
      (node (ref "SR0") (pin "12") (pinfunction "12_12") (pintype "passive"))
      (node (ref "SR1") (pin "12") (pinfunction "12_12") (pintype "passive"))
      (node (ref "SR10") (pin "12") (pinfunction "12_12") (pintype "passive"))
      (node (ref "SR11") (pin "12") (pinfunction "12_12") (pintype "passive"))
      (node (ref "SR12") (pin "12") (pinfunction "12_12") (pintype "passive"))
      (node (ref "SR13") (pin "12") (pinfunction "12_12") (pintype "passive"))
      (node (ref "SR14") (pin "12") (pinfunction "12_12") (pintype "passive"))
      (node (ref "SR15") (pin "12") (pinfunction "12_12") (pintype "passive"))
      (node (ref "SR16") (pin "12") (pinfunction "12_12") (pintype "passive"))
      (node (ref "SR17") (pin "12") (pinfunction "12_12") (pintype "passive"))
      (node (ref "SR18") (pin "12") (pinfunction "12_12") (pintype "passive"))
      (node (ref "SR19") (pin "12") (pinfunction "12_12") (pintype "passive"))
      (node (ref "SR2") (pin "12") (pinfunction "12_12") (pintype "passive"))
      (node (ref "SR3") (pin "12") (pinfunction "12_12") (pintype "passive"))
      (node (ref "SR4") (pin "12") (pinfunction "12_12") (pintype "passive"))
      (node (ref "SR5") (pin "12") (pinfunction "12_12") (pintype "passive"))
      (node (ref "SR6") (pin "12") (pinfunction "12_12") (pintype "passive"))
      (node (ref "SR7") (pin "12") (pinfunction "12_12") (pintype "passive"))
      (node (ref "SR8") (pin "12") (pinfunction "12_12") (pintype "passive"))
      (node (ref "SR9") (pin "12") (pinfunction "12_12") (pintype "passive"))
    )
    (net (code "161") (name "/TO_SR1") (class "Default")
      (node (ref "SR0") (pin "9") (pinfunction "9_9") (pintype "passive"))
      (node (ref "SR1") (pin "14") (pinfunction "14_14") (pintype "passive"))
    )
    (net (code "162") (name "/TO_SR2") (class "Default")
      (node (ref "SR1") (pin "9") (pinfunction "9_9") (pintype "passive"))
      (node (ref "SR2") (pin "14") (pinfunction "14_14") (pintype "passive"))
    )
    (net (code "163") (name "/TO_SR3") (class "Default")
      (node (ref "SR2") (pin "9") (pinfunction "9_9") (pintype "passive"))
      (node (ref "SR3") (pin "14") (pinfunction "14_14") (pintype "passive"))
    )
    (net (code "164") (name "/TO_SR4") (class "Default")
      (node (ref "SR3") (pin "9") (pinfunction "9_9") (pintype "passive"))
      (node (ref "SR4") (pin "14") (pinfunction "14_14") (pintype "passive"))
    )
    (net (code "165") (name "/TO_SR5") (class "Default")
      (node (ref "SR4") (pin "9") (pinfunction "9_9") (pintype "passive"))
      (node (ref "SR5") (pin "14") (pinfunction "14_14") (pintype "passive"))
    )
    (net (code "166") (name "/TO_SR6") (class "Default")
      (node (ref "SR5") (pin "9") (pinfunction "9_9") (pintype "passive"))
      (node (ref "SR6") (pin "14") (pinfunction "14_14") (pintype "passive"))
    )
    (net (code "167") (name "/TO_SR7") (class "Default")
      (node (ref "SR6") (pin "9") (pinfunction "9_9") (pintype "passive"))
      (node (ref "SR7") (pin "14") (pinfunction "14_14") (pintype "passive"))
    )
    (net (code "168") (name "/TO_SR8") (class "Default")
      (node (ref "SR7") (pin "9") (pinfunction "9_9") (pintype "passive"))
      (node (ref "SR8") (pin "14") (pinfunction "14_14") (pintype "passive"))
    )
    (net (code "169") (name "/TO_SR9") (class "Default")
      (node (ref "SR8") (pin "9") (pinfunction "9_9") (pintype "passive"))
      (node (ref "SR9") (pin "14") (pinfunction "14_14") (pintype "passive"))
    )
    (net (code "170") (name "/TO_SR10") (class "Default")
      (node (ref "SR10") (pin "14") (pinfunction "14_14") (pintype "passive"))
      (node (ref "SR9") (pin "9") (pinfunction "9_9") (pintype "passive"))
    )
    (net (code "171") (name "/TO_SR11") (class "Default")
      (node (ref "SR10") (pin "9") (pinfunction "9_9") (pintype "passive"))
      (node (ref "SR11") (pin "14") (pinfunction "14_14") (pintype "passive"))
    )
    (net (code "172") (name "/TO_SR12") (class "Default")
      (node (ref "SR11") (pin "9") (pinfunction "9_9") (pintype "passive"))
      (node (ref "SR12") (pin "14") (pinfunction "14_14") (pintype "passive"))
    )
    (net (code "173") (name "/TO_SR13") (class "Default")
      (node (ref "SR12") (pin "9") (pinfunction "9_9") (pintype "passive"))
      (node (ref "SR13") (pin "14") (pinfunction "14_14") (pintype "passive"))
    )
    (net (code "174") (name "/TO_SR14") (class "Default")
      (node (ref "SR13") (pin "9") (pinfunction "9_9") (pintype "passive"))
      (node (ref "SR14") (pin "14") (pinfunction "14_14") (pintype "passive"))
    )
    (net (code "175") (name "/TO_SR15") (class "Default")
      (node (ref "SR14") (pin "9") (pinfunction "9_9") (pintype "passive"))
      (node (ref "SR15") (pin "14") (pinfunction "14_14") (pintype "passive"))
    )
    (net (code "176") (name "/TO_SR16") (class "Default")
      (node (ref "SR15") (pin "9") (pinfunction "9_9") (pintype "passive"))
      (node (ref "SR16") (pin "14") (pinfunction "14_14") (pintype "passive"))
    )
    (net (code "177") (name "/TO_SR17") (class "Default")
      (node (ref "SR16") (pin "9") (pinfunction "9_9") (pintype "passive"))
      (node (ref "SR17") (pin "14") (pinfunction "14_14") (pintype "passive"))
    )
    (net (code "178") (name "/TO_SR18") (class "Default")
      (node (ref "SR17") (pin "9") (pinfunction "9_9") (pintype "passive"))
      (node (ref "SR18") (pin "14") (pinfunction "14_14") (pintype "passive"))
    )
    (net (code "179") (name "/TO_SR19") (class "Default")
      (node (ref "SR18") (pin "9") (pinfunction "9_9") (pintype "passive"))
      (node (ref "SR19") (pin "14") (pinfunction "14_14") (pintype "passive"))
    )
    (net (code "180") (name "12V") (class "Default")
      (node (ref "J12") (pin "2") (pinfunction "2_2") (pintype "passive"))
      (node (ref "J13") (pin "2") (pinfunction "2_2") (pintype "passive"))
      (node (ref "J14") (pin "2") (pinfunction "2_2") (pintype "passive"))
      (node (ref "J15") (pin "2") (pinfunction "2_2") (pintype "passive"))
      (node (ref "J16") (pin "2") (pinfunction "2_2") (pintype "passive"))
      (node (ref "J17") (pin "2") (pinfunction "2_2") (pintype "passive"))
      (node (ref "J18") (pin "2") (pinfunction "2_2") (pintype "passive"))
      (node (ref "J19") (pin "2") (pinfunction "2_2") (pintype "passive"))
      (node (ref "J20") (pin "2") (pinfunction "2_2") (pintype "passive"))
      (node (ref "J21") (pin "2") (pinfunction "2_2") (pintype "passive"))
      (node (ref "J22") (pin "2") (pinfunction "2_2") (pintype "passive"))
    )
    (net (code "181") (name "GND") (class "Default")
      (node (ref "J1") (pin "1") (pinfunction "1_1") (pintype "passive"))
      (node (ref "J10") (pin "1") (pinfunction "1_1") (pintype "passive"))
      (node (ref "J11") (pin "1") (pinfunction "1_1") (pintype "passive"))
      (node (ref "J12") (pin "1") (pinfunction "1_1") (pintype "passive"))
      (node (ref "J13") (pin "1") (pinfunction "1_1") (pintype "passive"))
      (node (ref "J14") (pin "1") (pinfunction "1_1") (pintype "passive"))
      (node (ref "J15") (pin "1") (pinfunction "1_1") (pintype "passive"))
      (node (ref "J16") (pin "1") (pinfunction "1_1") (pintype "passive"))
      (node (ref "J17") (pin "1") (pinfunction "1_1") (pintype "passive"))
      (node (ref "J18") (pin "1") (pinfunction "1_1") (pintype "passive"))
      (node (ref "J19") (pin "1") (pinfunction "1_1") (pintype "passive"))
      (node (ref "J2") (pin "1") (pinfunction "1_1") (pintype "passive"))
      (node (ref "J20") (pin "1") (pinfunction "1_1") (pintype "passive"))
      (node (ref "J21") (pin "1") (pinfunction "1_1") (pintype "passive"))
      (node (ref "J22") (pin "1") (pinfunction "1_1") (pintype "passive"))
      (node (ref "J3") (pin "1") (pinfunction "1_1") (pintype "passive"))
      (node (ref "J4") (pin "1") (pinfunction "1_1") (pintype "passive"))
      (node (ref "J5") (pin "1") (pinfunction "1_1") (pintype "passive"))
      (node (ref "J6") (pin "1") (pinfunction "1_1") (pintype "passive"))
      (node (ref "J7") (pin "1") (pinfunction "1_1") (pintype "passive"))
      (node (ref "J8") (pin "1") (pinfunction "1_1") (pintype "passive"))
      (node (ref "J9") (pin "1") (pinfunction "1_1") (pintype "passive"))
      (node (ref "P10") (pin "2") (pinfunction "2_2") (pintype "passive"))
      (node (ref "SR0") (pin "13") (pinfunction "13_13") (pintype "passive"))
      (node (ref "SR0") (pin "8") (pinfunction "8_8") (pintype "passive"))
      (node (ref "SR1") (pin "13") (pinfunction "13_13") (pintype "passive"))
      (node (ref "SR1") (pin "8") (pinfunction "8_8") (pintype "passive"))
      (node (ref "SR10") (pin "13") (pinfunction "13_13") (pintype "passive"))
      (node (ref "SR10") (pin "8") (pinfunction "8_8") (pintype "passive"))
      (node (ref "SR11") (pin "13") (pinfunction "13_13") (pintype "passive"))
      (node (ref "SR11") (pin "8") (pinfunction "8_8") (pintype "passive"))
      (node (ref "SR12") (pin "13") (pinfunction "13_13") (pintype "passive"))
      (node (ref "SR12") (pin "8") (pinfunction "8_8") (pintype "passive"))
      (node (ref "SR13") (pin "13") (pinfunction "13_13") (pintype "passive"))
      (node (ref "SR13") (pin "8") (pinfunction "8_8") (pintype "passive"))
      (node (ref "SR14") (pin "13") (pinfunction "13_13") (pintype "passive"))
      (node (ref "SR14") (pin "8") (pinfunction "8_8") (pintype "passive"))
      (node (ref "SR15") (pin "13") (pinfunction "13_13") (pintype "passive"))
      (node (ref "SR15") (pin "8") (pinfunction "8_8") (pintype "passive"))
      (node (ref "SR16") (pin "13") (pinfunction "13_13") (pintype "passive"))
      (node (ref "SR16") (pin "8") (pinfunction "8_8") (pintype "passive"))
      (node (ref "SR17") (pin "13") (pinfunction "13_13") (pintype "passive"))
      (node (ref "SR17") (pin "8") (pinfunction "8_8") (pintype "passive"))
      (node (ref "SR18") (pin "13") (pinfunction "13_13") (pintype "passive"))
      (node (ref "SR18") (pin "8") (pinfunction "8_8") (pintype "passive"))
      (node (ref "SR19") (pin "13") (pinfunction "13_13") (pintype "passive"))
      (node (ref "SR19") (pin "8") (pinfunction "8_8") (pintype "passive"))
      (node (ref "SR2") (pin "13") (pinfunction "13_13") (pintype "passive"))
      (node (ref "SR2") (pin "8") (pinfunction "8_8") (pintype "passive"))
      (node (ref "SR3") (pin "13") (pinfunction "13_13") (pintype "passive"))
      (node (ref "SR3") (pin "8") (pinfunction "8_8") (pintype "passive"))
      (node (ref "SR4") (pin "13") (pinfunction "13_13") (pintype "passive"))
      (node (ref "SR4") (pin "8") (pinfunction "8_8") (pintype "passive"))
      (node (ref "SR5") (pin "13") (pinfunction "13_13") (pintype "passive"))
      (node (ref "SR5") (pin "8") (pinfunction "8_8") (pintype "passive"))
      (node (ref "SR6") (pin "13") (pinfunction "13_13") (pintype "passive"))
      (node (ref "SR6") (pin "8") (pinfunction "8_8") (pintype "passive"))
      (node (ref "SR7") (pin "13") (pinfunction "13_13") (pintype "passive"))
      (node (ref "SR7") (pin "8") (pinfunction "8_8") (pintype "passive"))
      (node (ref "SR8") (pin "13") (pinfunction "13_13") (pintype "passive"))
      (node (ref "SR8") (pin "8") (pinfunction "8_8") (pintype "passive"))
      (node (ref "SR9") (pin "13") (pinfunction "13_13") (pintype "passive"))
      (node (ref "SR9") (pin "8") (pinfunction "8_8") (pintype "passive"))
    )
    (net (code "182") (name "Net-(D1-A)") (class "Default")
      (node (ref "D1") (pin "1") (pinfunction "A_1") (pintype "input"))
      (node (ref "P11") (pin "1") (pinfunction "1_1") (pintype "passive"))
    )
    (net (code "183") (name "Net-(D1-K)") (class "Default")
      (node (ref "D1") (pin "2") (pinfunction "K_2") (pintype "output"))
      (node (ref "D13") (pin "2") (pinfunction "K_2") (pintype "output"))
      (node (ref "D17") (pin "2") (pinfunction "K_2") (pintype "output"))
      (node (ref "D21") (pin "2") (pinfunction "K_2") (pintype "output"))
      (node (ref "D25") (pin "2") (pinfunction "K_2") (pintype "output"))
      (node (ref "D29") (pin "2") (pinfunction "K_2") (pintype "output"))
      (node (ref "D33") (pin "2") (pinfunction "K_2") (pintype "output"))
      (node (ref "D37") (pin "2") (pinfunction "K_2") (pintype "output"))
      (node (ref "D5") (pin "2") (pinfunction "K_2") (pintype "output"))
      (node (ref "D9") (pin "2") (pinfunction "K_2") (pintype "output"))
      (node (ref "R1") (pin "1") (pinfunction "1_1") (pintype "passive"))
    )
    (net (code "184") (name "Net-(D2-A)") (class "Default")
      (node (ref "D2") (pin "1") (pinfunction "A_1") (pintype "input"))
      (node (ref "P11") (pin "2") (pinfunction "2_2") (pintype "passive"))
    )
    (net (code "185") (name "Net-(D3-A)") (class "Default")
      (node (ref "D3") (pin "1") (pinfunction "A_1") (pintype "input"))
      (node (ref "P11") (pin "3") (pinfunction "3_3") (pintype "passive"))
    )
    (net (code "186") (name "Net-(D4-A)") (class "Default")
      (node (ref "D4") (pin "1") (pinfunction "A_1") (pintype "input"))
      (node (ref "P11") (pin "4") (pinfunction "4_4") (pintype "passive"))
    )
    (net (code "187") (name "Net-(D5-A)") (class "Default")
      (node (ref "D5") (pin "1") (pinfunction "A_1") (pintype "input"))
      (node (ref "P12") (pin "1") (pinfunction "1_1") (pintype "passive"))
    )
    (net (code "188") (name "Net-(D6-A)") (class "Default")
      (node (ref "D6") (pin "1") (pinfunction "A_1") (pintype "input"))
      (node (ref "P12") (pin "2") (pinfunction "2_2") (pintype "passive"))
    )
    (net (code "189") (name "Net-(D7-A)") (class "Default")
      (node (ref "D7") (pin "1") (pinfunction "A_1") (pintype "input"))
      (node (ref "P12") (pin "3") (pinfunction "3_3") (pintype "passive"))
    )
    (net (code "190") (name "Net-(D8-A)") (class "Default")
      (node (ref "D8") (pin "1") (pinfunction "A_1") (pintype "input"))
      (node (ref "P12") (pin "4") (pinfunction "4_4") (pintype "passive"))
    )
    (net (code "191") (name "Net-(D9-A)") (class "Default")
      (node (ref "D9") (pin "1") (pinfunction "A_1") (pintype "input"))
      (node (ref "P13") (pin "1") (pinfunction "1_1") (pintype "passive"))
    )
    (net (code "192") (name "Net-(D10-A)") (class "Default")
      (node (ref "D10") (pin "1") (pinfunction "A_1") (pintype "input"))
      (node (ref "P13") (pin "2") (pinfunction "2_2") (pintype "passive"))
    )
    (net (code "193") (name "Net-(D10-K)") (class "Default")
      (node (ref "D10") (pin "2") (pinfunction "K_2") (pintype "output"))
      (node (ref "D18") (pin "2") (pinfunction "K_2") (pintype "output"))
      (node (ref "D2") (pin "2") (pinfunction "K_2") (pintype "output"))
      (node (ref "D22") (pin "2") (pinfunction "K_2") (pintype "output"))
      (node (ref "D26") (pin "2") (pinfunction "K_2") (pintype "output"))
      (node (ref "D30") (pin "2") (pinfunction "K_2") (pintype "output"))
      (node (ref "D34") (pin "2") (pinfunction "K_2") (pintype "output"))
      (node (ref "D38") (pin "2") (pinfunction "K_2") (pintype "output"))
      (node (ref "D6") (pin "2") (pinfunction "K_2") (pintype "output"))
      (node (ref "R2") (pin "1") (pinfunction "1_1") (pintype "passive"))
    )
    (net (code "194") (name "Net-(D11-A)") (class "Default")
      (node (ref "D11") (pin "1") (pinfunction "A_1") (pintype "input"))
      (node (ref "P13") (pin "3") (pinfunction "3_3") (pintype "passive"))
    )
    (net (code "195") (name "Net-(D11-K)") (class "Default")
      (node (ref "D11") (pin "2") (pinfunction "K_2") (pintype "output"))
      (node (ref "D14") (pin "2") (pinfunction "K_2") (pintype "output"))
      (node (ref "D19") (pin "2") (pinfunction "K_2") (pintype "output"))
      (node (ref "D23") (pin "2") (pinfunction "K_2") (pintype "output"))
      (node (ref "D27") (pin "2") (pinfunction "K_2") (pintype "output"))
      (node (ref "D3") (pin "2") (pinfunction "K_2") (pintype "output"))
      (node (ref "D31") (pin "2") (pinfunction "K_2") (pintype "output"))
      (node (ref "D35") (pin "2") (pinfunction "K_2") (pintype "output"))
      (node (ref "D39") (pin "2") (pinfunction "K_2") (pintype "output"))
      (node (ref "D7") (pin "2") (pinfunction "K_2") (pintype "output"))
      (node (ref "R3") (pin "1") (pinfunction "1_1") (pintype "passive"))
    )
    (net (code "196") (name "Net-(D12-A)") (class "Default")
      (node (ref "D12") (pin "1") (pinfunction "A_1") (pintype "input"))
      (node (ref "P13") (pin "4") (pinfunction "4_4") (pintype "passive"))
    )
    (net (code "197") (name "Net-(D12-K)") (class "Default")
      (node (ref "D12") (pin "2") (pinfunction "K_2") (pintype "output"))
      (node (ref "D15") (pin "2") (pinfunction "K_2") (pintype "output"))
      (node (ref "D16") (pin "2") (pinfunction "K_2") (pintype "output"))
      (node (ref "D20") (pin "2") (pinfunction "K_2") (pintype "output"))
      (node (ref "D24") (pin "2") (pinfunction "K_2") (pintype "output"))
      (node (ref "D28") (pin "2") (pinfunction "K_2") (pintype "output"))
      (node (ref "D32") (pin "2") (pinfunction "K_2") (pintype "output"))
      (node (ref "D36") (pin "2") (pinfunction "K_2") (pintype "output"))
      (node (ref "D4") (pin "2") (pinfunction "K_2") (pintype "output"))
      (node (ref "D40") (pin "2") (pinfunction "K_2") (pintype "output"))
      (node (ref "D8") (pin "2") (pinfunction "K_2") (pintype "output"))
      (node (ref "R4") (pin "1") (pinfunction "1_1") (pintype "passive"))
    )
    (net (code "198") (name "Net-(D13-A)") (class "Default")
      (node (ref "D13") (pin "1") (pinfunction "A_1") (pintype "input"))
      (node (ref "P14") (pin "1") (pinfunction "1_1") (pintype "passive"))
    )
    (net (code "199") (name "Net-(D14-A)") (class "Default")
      (node (ref "D14") (pin "1") (pinfunction "A_1") (pintype "input"))
      (node (ref "P14") (pin "2") (pinfunction "2_2") (pintype "passive"))
    )
    (net (code "200") (name "Net-(D15-A)") (class "Default")
      (node (ref "D15") (pin "1") (pinfunction "A_1") (pintype "input"))
      (node (ref "P14") (pin "3") (pinfunction "3_3") (pintype "passive"))
    )
    (net (code "201") (name "Net-(D16-A)") (class "Default")
      (node (ref "D16") (pin "1") (pinfunction "A_1") (pintype "input"))
      (node (ref "P14") (pin "4") (pinfunction "4_4") (pintype "passive"))
    )
    (net (code "202") (name "Net-(D17-A)") (class "Default")
      (node (ref "D17") (pin "1") (pinfunction "A_1") (pintype "input"))
      (node (ref "P15") (pin "1") (pinfunction "1_1") (pintype "passive"))
    )
    (net (code "203") (name "Net-(D18-A)") (class "Default")
      (node (ref "D18") (pin "1") (pinfunction "A_1") (pintype "input"))
      (node (ref "P15") (pin "2") (pinfunction "2_2") (pintype "passive"))
    )
    (net (code "204") (name "Net-(D19-A)") (class "Default")
      (node (ref "D19") (pin "1") (pinfunction "A_1") (pintype "input"))
      (node (ref "P15") (pin "3") (pinfunction "3_3") (pintype "passive"))
    )
    (net (code "205") (name "Net-(D20-A)") (class "Default")
      (node (ref "D20") (pin "1") (pinfunction "A_1") (pintype "input"))
      (node (ref "P15") (pin "4") (pinfunction "4_4") (pintype "passive"))
    )
    (net (code "206") (name "Net-(D21-A)") (class "Default")
      (node (ref "D21") (pin "1") (pinfunction "A_1") (pintype "input"))
      (node (ref "P16") (pin "1") (pinfunction "1_1") (pintype "passive"))
    )
    (net (code "207") (name "Net-(D22-A)") (class "Default")
      (node (ref "D22") (pin "1") (pinfunction "A_1") (pintype "input"))
      (node (ref "P16") (pin "2") (pinfunction "2_2") (pintype "passive"))
    )
    (net (code "208") (name "Net-(D23-A)") (class "Default")
      (node (ref "D23") (pin "1") (pinfunction "A_1") (pintype "input"))
      (node (ref "P16") (pin "3") (pinfunction "3_3") (pintype "passive"))
    )
    (net (code "209") (name "Net-(D24-A)") (class "Default")
      (node (ref "D24") (pin "1") (pinfunction "A_1") (pintype "input"))
      (node (ref "P16") (pin "4") (pinfunction "4_4") (pintype "passive"))
    )
    (net (code "210") (name "Net-(D25-A)") (class "Default")
      (node (ref "D25") (pin "1") (pinfunction "A_1") (pintype "input"))
      (node (ref "P17") (pin "1") (pinfunction "1_1") (pintype "passive"))
    )
    (net (code "211") (name "Net-(D26-A)") (class "Default")
      (node (ref "D26") (pin "1") (pinfunction "A_1") (pintype "input"))
      (node (ref "P17") (pin "2") (pinfunction "2_2") (pintype "passive"))
    )
    (net (code "212") (name "Net-(D27-A)") (class "Default")
      (node (ref "D27") (pin "1") (pinfunction "A_1") (pintype "input"))
      (node (ref "P17") (pin "3") (pinfunction "3_3") (pintype "passive"))
    )
    (net (code "213") (name "Net-(D28-A)") (class "Default")
      (node (ref "D28") (pin "1") (pinfunction "A_1") (pintype "input"))
      (node (ref "P17") (pin "4") (pinfunction "4_4") (pintype "passive"))
    )
    (net (code "214") (name "Net-(D29-A)") (class "Default")
      (node (ref "D29") (pin "1") (pinfunction "A_1") (pintype "input"))
      (node (ref "P18") (pin "1") (pinfunction "1_1") (pintype "passive"))
    )
    (net (code "215") (name "Net-(D30-A)") (class "Default")
      (node (ref "D30") (pin "1") (pinfunction "A_1") (pintype "input"))
      (node (ref "P18") (pin "2") (pinfunction "2_2") (pintype "passive"))
    )
    (net (code "216") (name "Net-(D31-A)") (class "Default")
      (node (ref "D31") (pin "1") (pinfunction "A_1") (pintype "input"))
      (node (ref "P18") (pin "3") (pinfunction "3_3") (pintype "passive"))
    )
    (net (code "217") (name "Net-(D32-A)") (class "Default")
      (node (ref "D32") (pin "1") (pinfunction "A_1") (pintype "input"))
      (node (ref "P18") (pin "4") (pinfunction "4_4") (pintype "passive"))
    )
    (net (code "218") (name "Net-(D33-A)") (class "Default")
      (node (ref "D33") (pin "1") (pinfunction "A_1") (pintype "input"))
      (node (ref "P19") (pin "1") (pinfunction "1_1") (pintype "passive"))
    )
    (net (code "219") (name "Net-(D34-A)") (class "Default")
      (node (ref "D34") (pin "1") (pinfunction "A_1") (pintype "input"))
      (node (ref "P19") (pin "2") (pinfunction "2_2") (pintype "passive"))
    )
    (net (code "220") (name "Net-(D35-A)") (class "Default")
      (node (ref "D35") (pin "1") (pinfunction "A_1") (pintype "input"))
      (node (ref "P19") (pin "3") (pinfunction "3_3") (pintype "passive"))
    )
    (net (code "221") (name "Net-(D36-A)") (class "Default")
      (node (ref "D36") (pin "1") (pinfunction "A_1") (pintype "input"))
      (node (ref "P19") (pin "4") (pinfunction "4_4") (pintype "passive"))
    )
    (net (code "222") (name "Net-(D37-A)") (class "Default")
      (node (ref "D37") (pin "1") (pinfunction "A_1") (pintype "input"))
      (node (ref "P20") (pin "1") (pinfunction "1_1") (pintype "passive"))
    )
    (net (code "223") (name "Net-(D38-A)") (class "Default")
      (node (ref "D38") (pin "1") (pinfunction "A_1") (pintype "input"))
      (node (ref "P20") (pin "2") (pinfunction "2_2") (pintype "passive"))
    )
    (net (code "224") (name "Net-(D39-A)") (class "Default")
      (node (ref "D39") (pin "1") (pinfunction "A_1") (pintype "input"))
      (node (ref "P20") (pin "3") (pinfunction "3_3") (pintype "passive"))
    )
    (net (code "225") (name "Net-(D40-A)") (class "Default")
      (node (ref "D40") (pin "1") (pinfunction "A_1") (pintype "input"))
      (node (ref "P20") (pin "4") (pinfunction "4_4") (pintype "passive"))
    )
    (net (code "226") (name "Net-(P21-Pad1)") (class "Default")
      (node (ref "P21") (pin "1") (pinfunction "1_1") (pintype "passive"))
      (node (ref "R1") (pin "2") (pinfunction "2_2") (pintype "passive"))
    )
    (net (code "227") (name "Net-(P21-Pad2)") (class "Default")
      (node (ref "P21") (pin "2") (pinfunction "2_2") (pintype "passive"))
      (node (ref "R2") (pin "2") (pinfunction "2_2") (pintype "passive"))
    )
    (net (code "228") (name "Net-(P21-Pad3)") (class "Default")
      (node (ref "P21") (pin "3") (pinfunction "3_3") (pintype "passive"))
      (node (ref "R3") (pin "2") (pinfunction "2_2") (pintype "passive"))
    )
    (net (code "229") (name "Net-(P21-Pad4)") (class "Default")
      (node (ref "P21") (pin "4") (pinfunction "4_4") (pintype "passive"))
      (node (ref "R4") (pin "2") (pinfunction "2_2") (pintype "passive"))
    )
    (net (code "230") (name "VCC") (class "Default")
      (node (ref "J1") (pin "2") (pinfunction "2_2") (pintype "passive"))
      (node (ref "J10") (pin "2") (pinfunction "2_2") (pintype "passive"))
      (node (ref "J11") (pin "2") (pinfunction "2_2") (pintype "passive"))
      (node (ref "J2") (pin "2") (pinfunction "2_2") (pintype "passive"))
      (node (ref "J3") (pin "2") (pinfunction "2_2") (pintype "passive"))
      (node (ref "J4") (pin "2") (pinfunction "2_2") (pintype "passive"))
      (node (ref "J5") (pin "2") (pinfunction "2_2") (pintype "passive"))
      (node (ref "J6") (pin "2") (pinfunction "2_2") (pintype "passive"))
      (node (ref "J7") (pin "2") (pinfunction "2_2") (pintype "passive"))
      (node (ref "J8") (pin "2") (pinfunction "2_2") (pintype "passive"))
      (node (ref "J9") (pin "2") (pinfunction "2_2") (pintype "passive"))
      (node (ref "P10") (pin "1") (pinfunction "1_1") (pintype "passive"))
      (node (ref "SR0") (pin "10") (pinfunction "10_10") (pintype "passive"))
      (node (ref "SR0") (pin "16") (pinfunction "16_16") (pintype "passive"))
      (node (ref "SR1") (pin "10") (pinfunction "10_10") (pintype "passive"))
      (node (ref "SR1") (pin "16") (pinfunction "16_16") (pintype "passive"))
      (node (ref "SR10") (pin "10") (pinfunction "10_10") (pintype "passive"))
      (node (ref "SR10") (pin "16") (pinfunction "16_16") (pintype "passive"))
      (node (ref "SR11") (pin "10") (pinfunction "10_10") (pintype "passive"))
      (node (ref "SR11") (pin "16") (pinfunction "16_16") (pintype "passive"))
      (node (ref "SR12") (pin "10") (pinfunction "10_10") (pintype "passive"))
      (node (ref "SR12") (pin "16") (pinfunction "16_16") (pintype "passive"))
      (node (ref "SR13") (pin "10") (pinfunction "10_10") (pintype "passive"))
      (node (ref "SR13") (pin "16") (pinfunction "16_16") (pintype "passive"))
      (node (ref "SR14") (pin "10") (pinfunction "10_10") (pintype "passive"))
      (node (ref "SR14") (pin "16") (pinfunction "16_16") (pintype "passive"))
      (node (ref "SR15") (pin "10") (pinfunction "10_10") (pintype "passive"))
      (node (ref "SR15") (pin "16") (pinfunction "16_16") (pintype "passive"))
      (node (ref "SR16") (pin "10") (pinfunction "10_10") (pintype "passive"))
      (node (ref "SR16") (pin "16") (pinfunction "16_16") (pintype "passive"))
      (node (ref "SR17") (pin "10") (pinfunction "10_10") (pintype "passive"))
      (node (ref "SR17") (pin "16") (pinfunction "16_16") (pintype "passive"))
      (node (ref "SR18") (pin "10") (pinfunction "10_10") (pintype "passive"))
      (node (ref "SR18") (pin "16") (pinfunction "16_16") (pintype "passive"))
      (node (ref "SR19") (pin "10") (pinfunction "10_10") (pintype "passive"))
      (node (ref "SR19") (pin "16") (pinfunction "16_16") (pintype "passive"))
      (node (ref "SR2") (pin "10") (pinfunction "10_10") (pintype "passive"))
      (node (ref "SR2") (pin "16") (pinfunction "16_16") (pintype "passive"))
      (node (ref "SR3") (pin "10") (pinfunction "10_10") (pintype "passive"))
      (node (ref "SR3") (pin "16") (pinfunction "16_16") (pintype "passive"))
      (node (ref "SR4") (pin "10") (pinfunction "10_10") (pintype "passive"))
      (node (ref "SR4") (pin "16") (pinfunction "16_16") (pintype "passive"))
      (node (ref "SR5") (pin "10") (pinfunction "10_10") (pintype "passive"))
      (node (ref "SR5") (pin "16") (pinfunction "16_16") (pintype "passive"))
      (node (ref "SR6") (pin "10") (pinfunction "10_10") (pintype "passive"))
      (node (ref "SR6") (pin "16") (pinfunction "16_16") (pintype "passive"))
      (node (ref "SR7") (pin "10") (pinfunction "10_10") (pintype "passive"))
      (node (ref "SR7") (pin "16") (pinfunction "16_16") (pintype "passive"))
      (node (ref "SR8") (pin "10") (pinfunction "10_10") (pintype "passive"))
      (node (ref "SR8") (pin "16") (pinfunction "16_16") (pintype "passive"))
      (node (ref "SR9") (pin "10") (pinfunction "10_10") (pintype "passive"))
      (node (ref "SR9") (pin "16") (pinfunction "16_16") (pintype "passive"))
    )
    (net (code "231") (name "unconnected-(SR19-Pad9)") (class "Default")
      (node (ref "SR19") (pin "9") (pinfunction "9_9") (pintype "passive"))
    )
  )
)
